# Page_1.net
KiCad netlist of a schematic drawn in Altium Designer
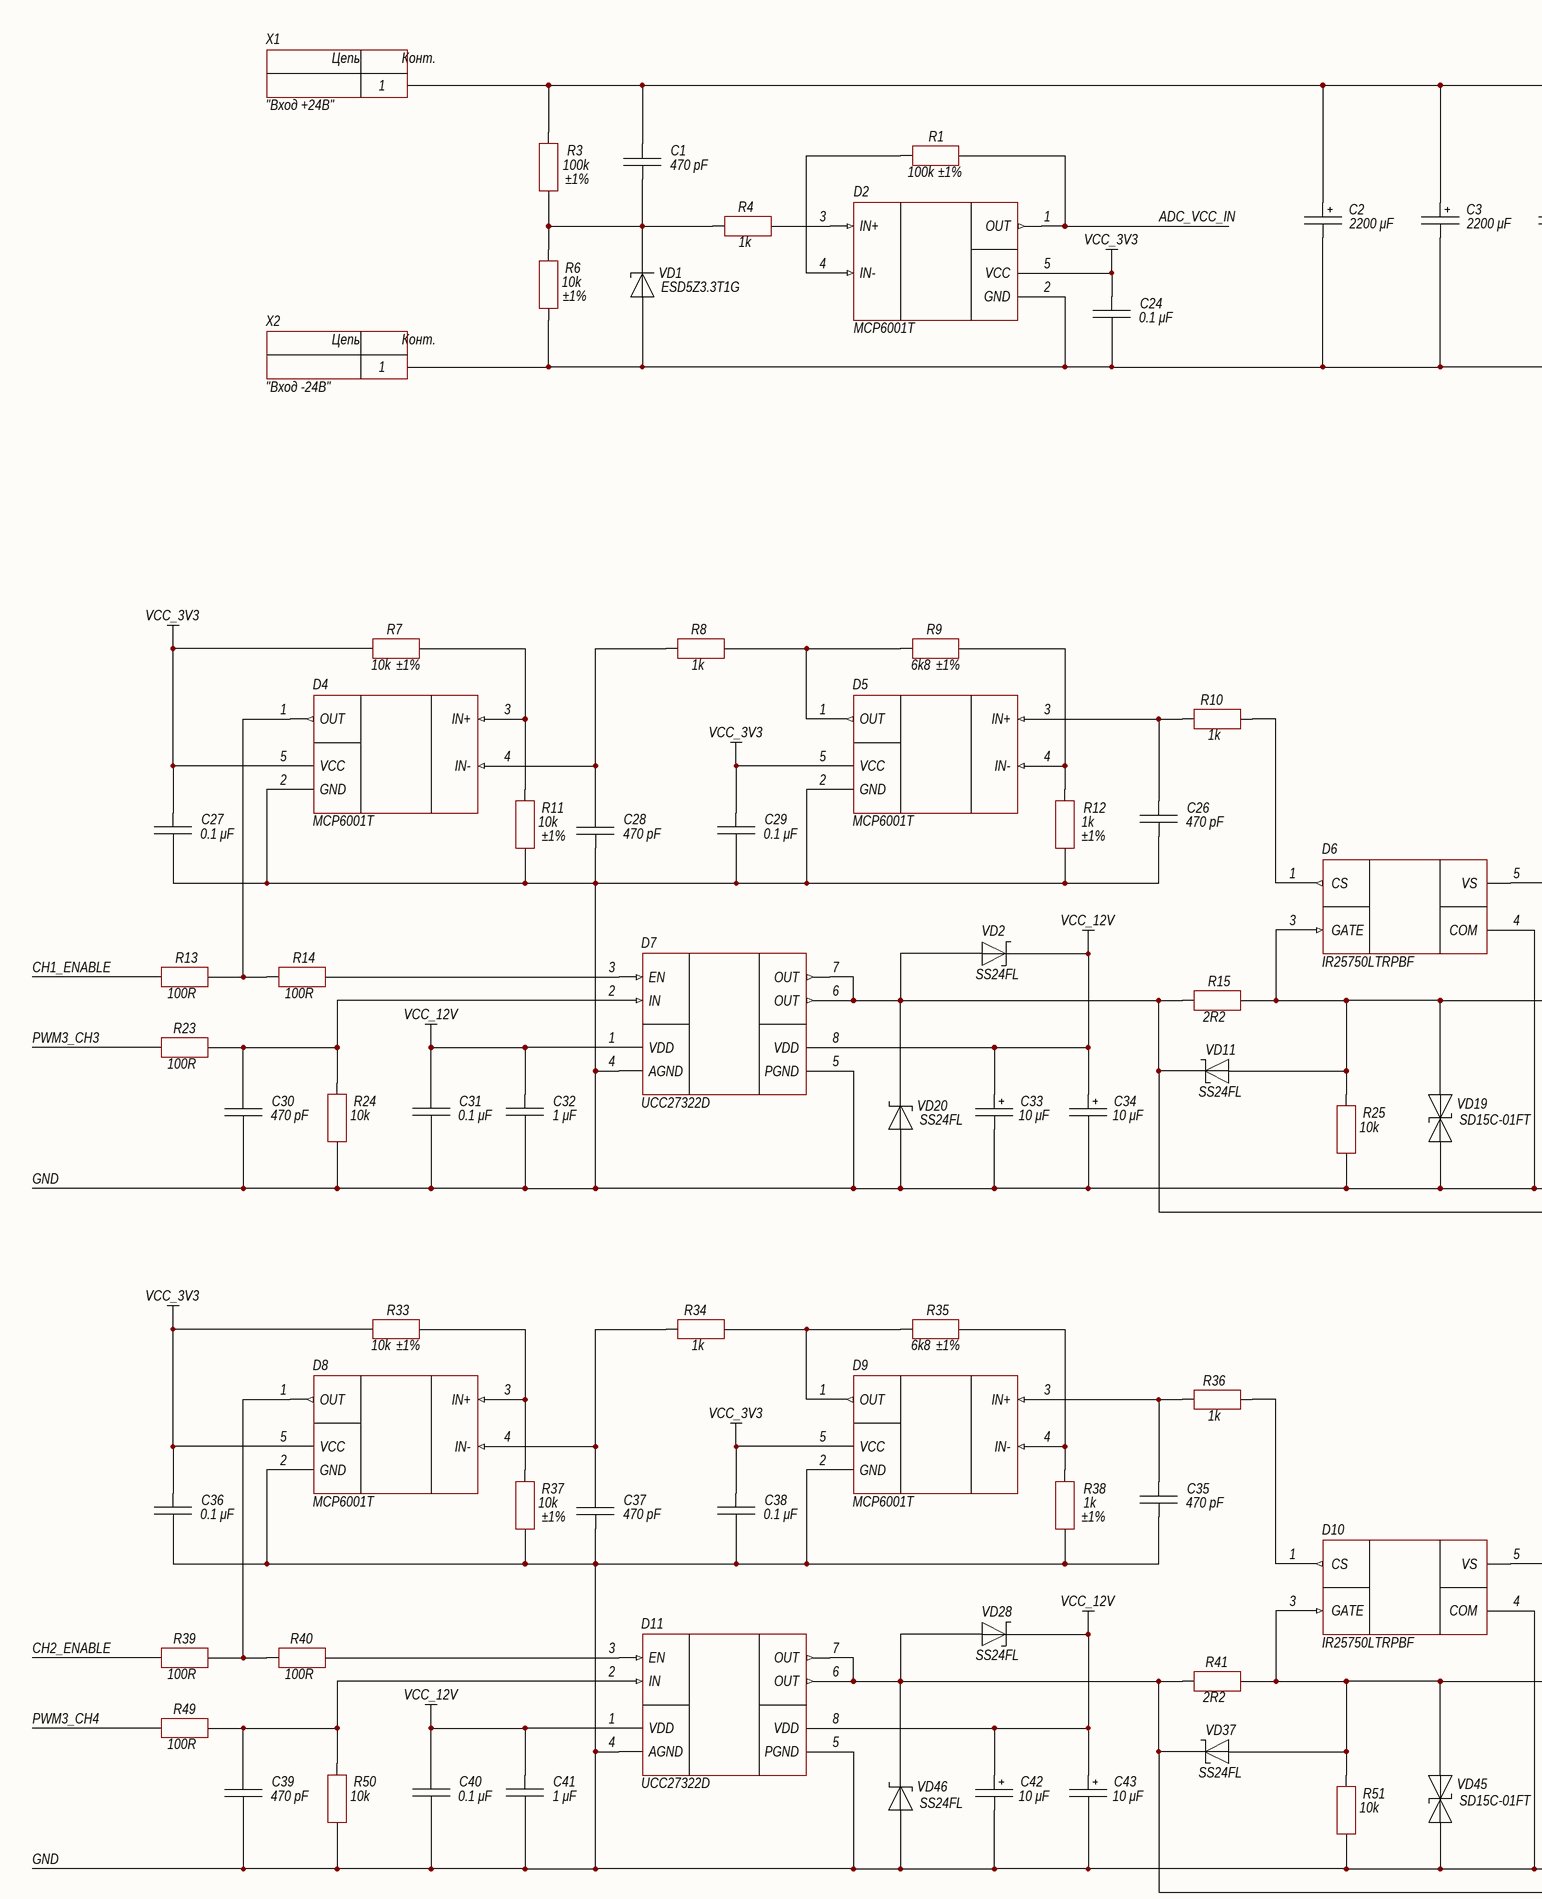
[diagram p0: Page 1.SchDoc, top left]
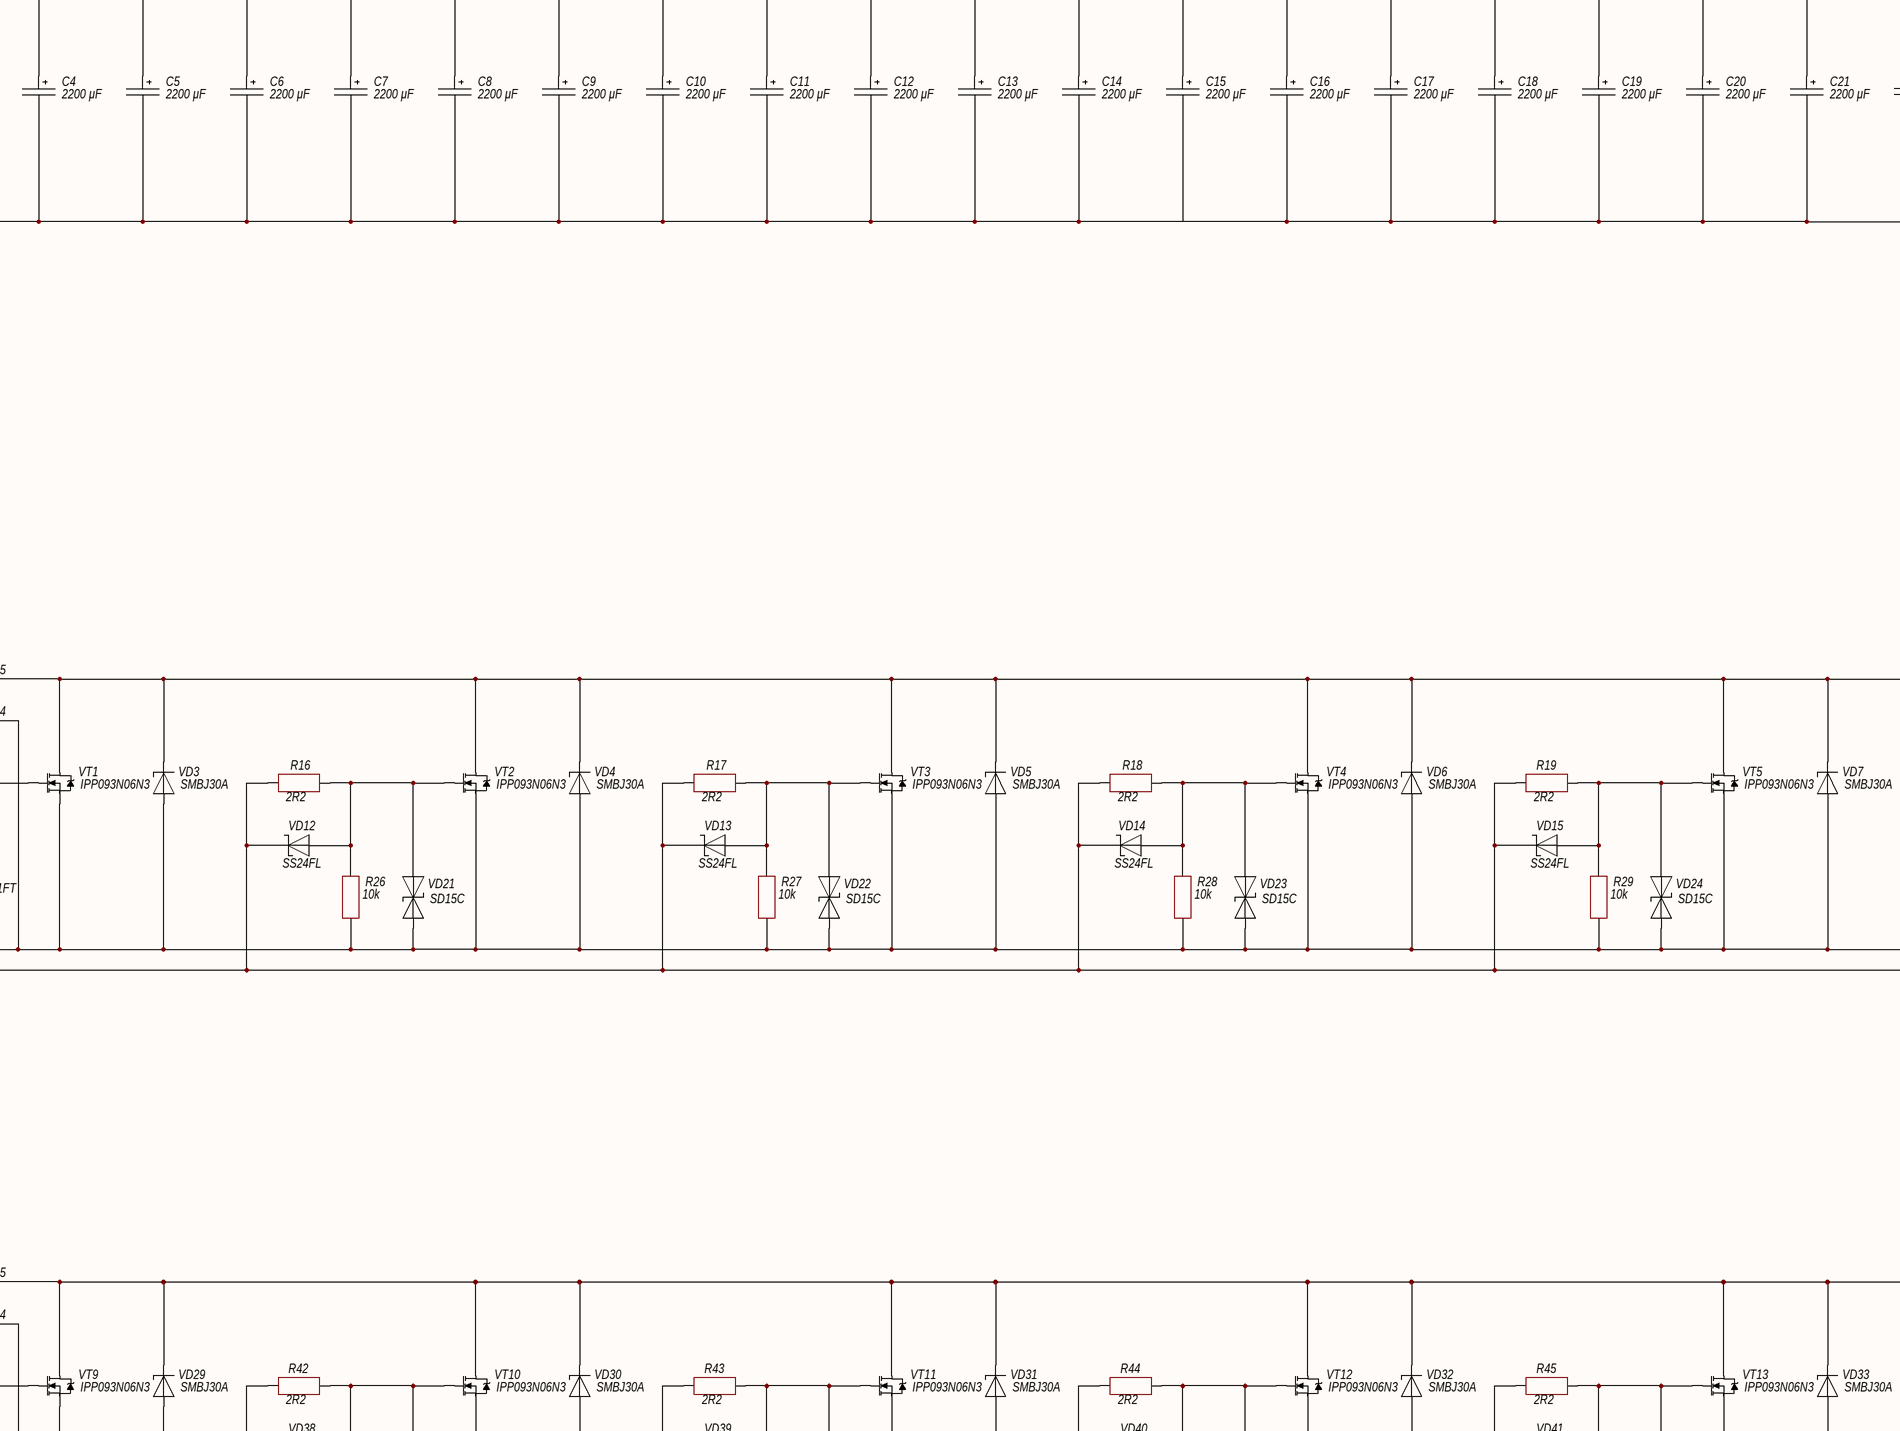
[diagram p1: Page 1.SchDoc, top middle]
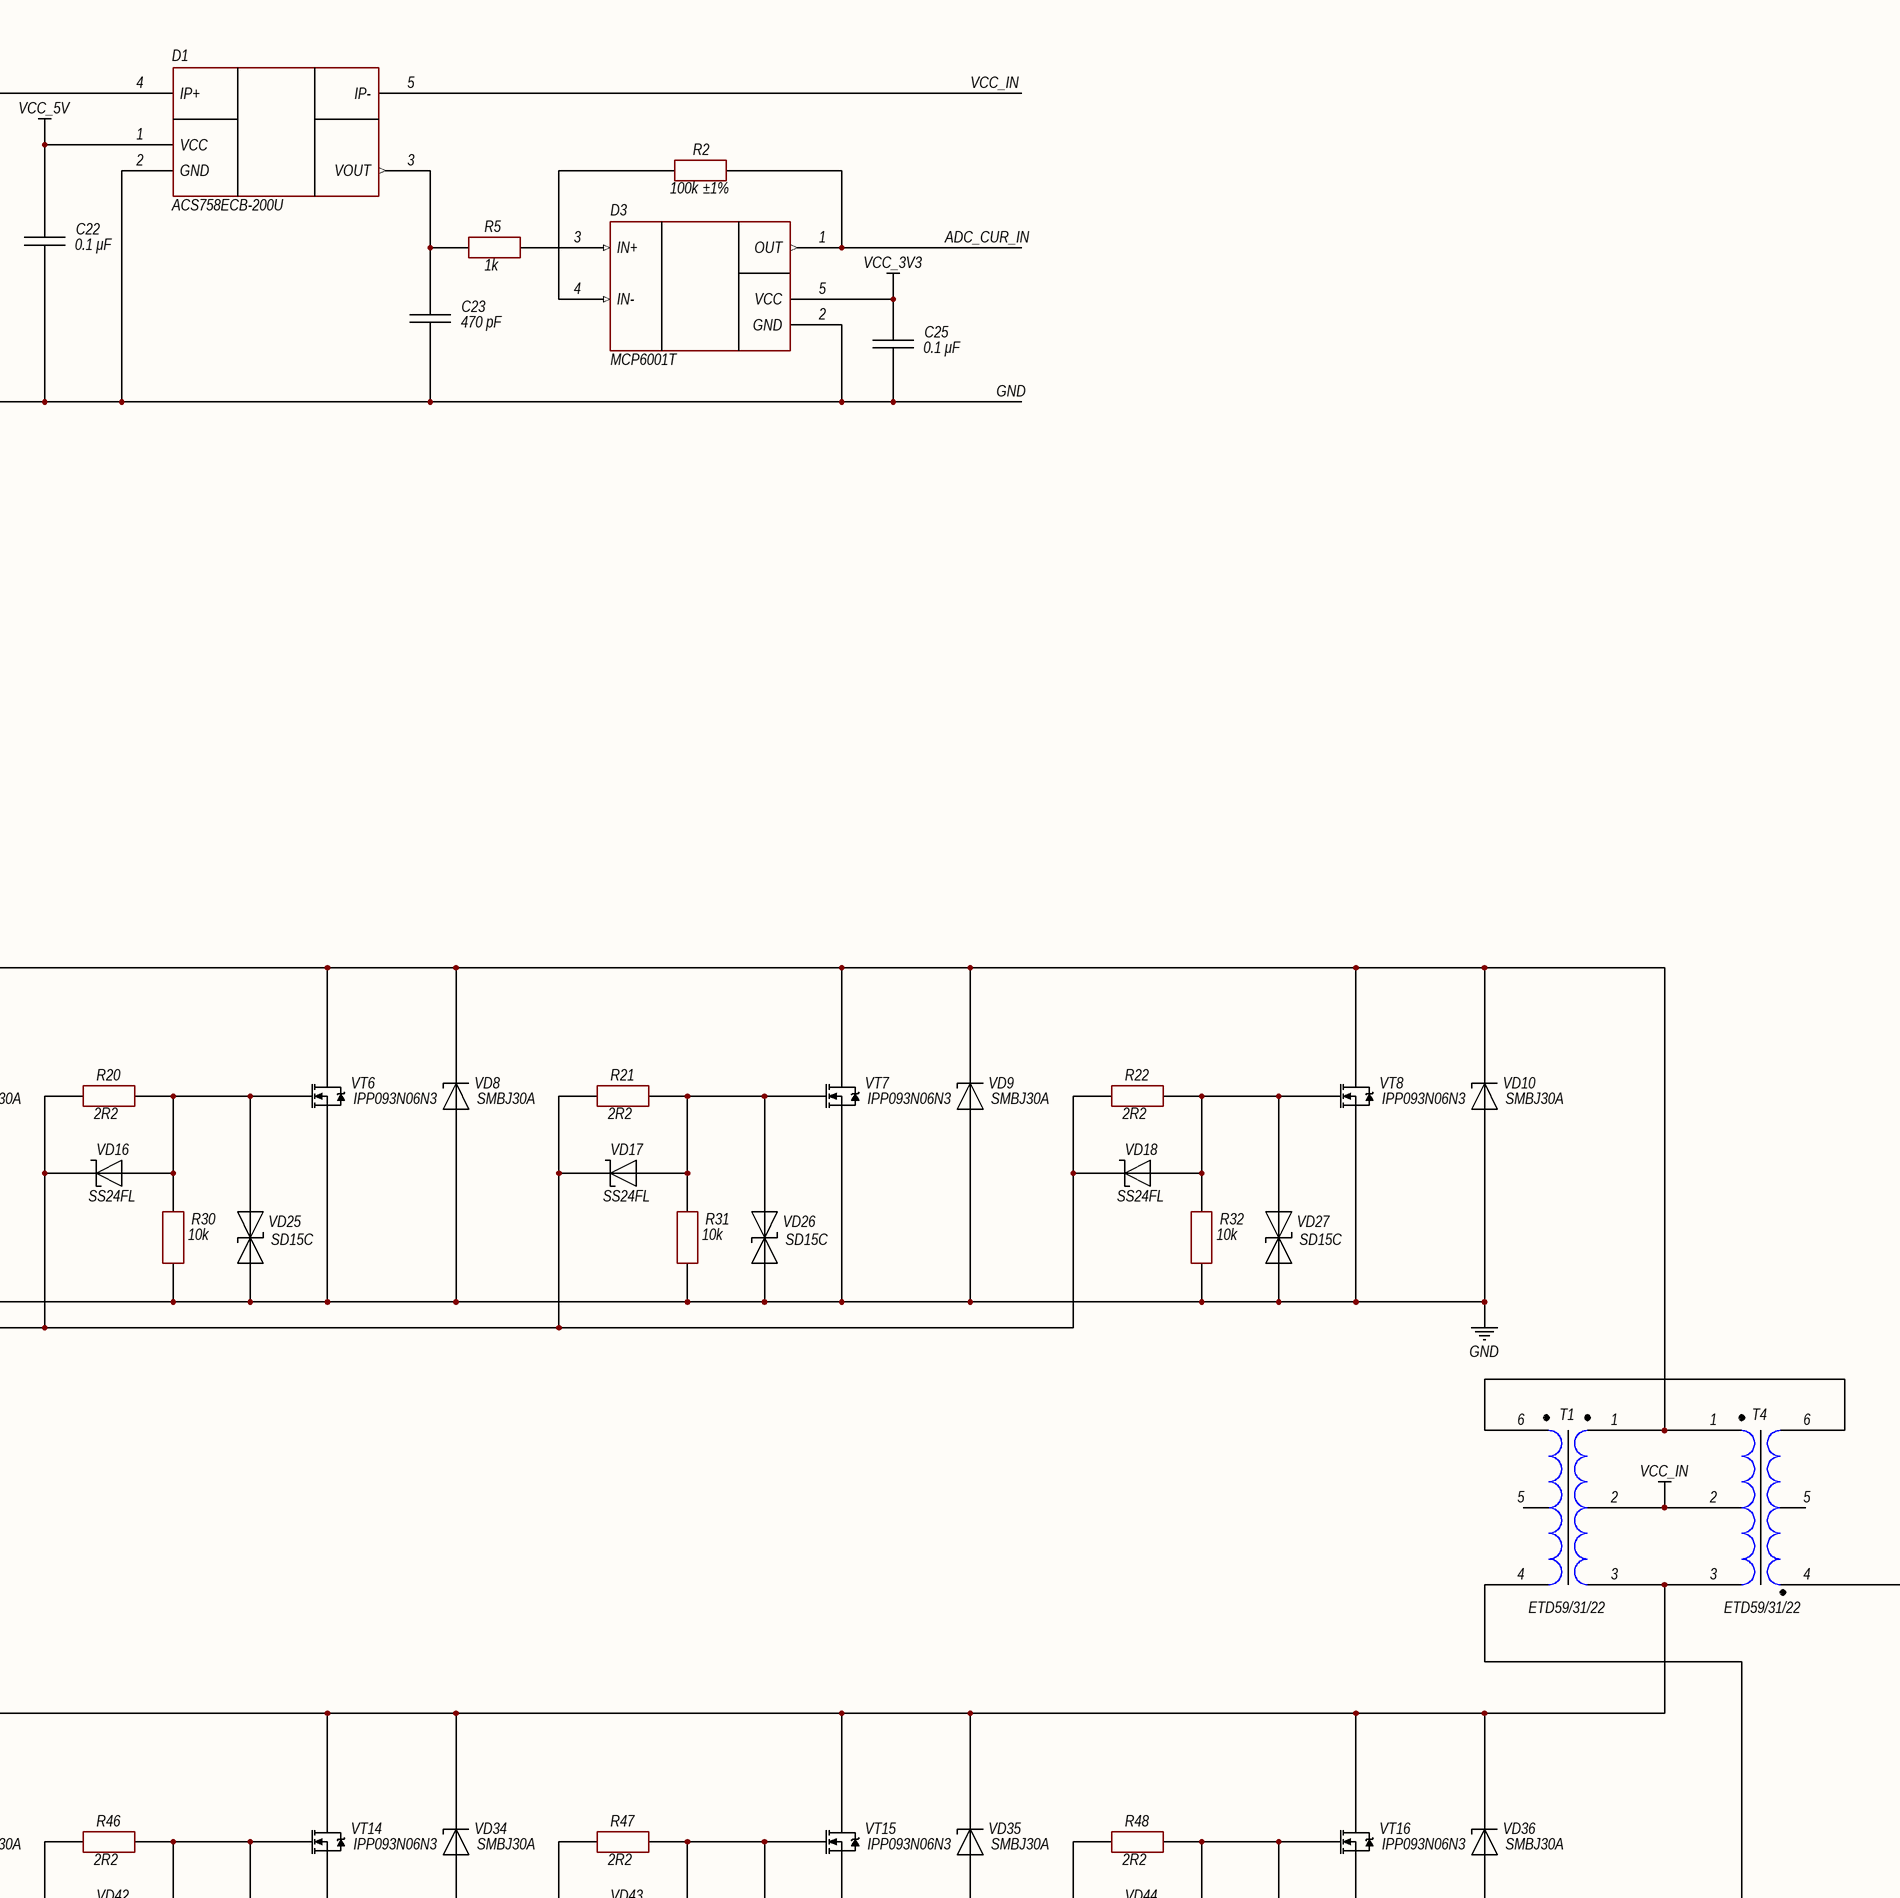
[diagram p2: Page 1.SchDoc, top right]
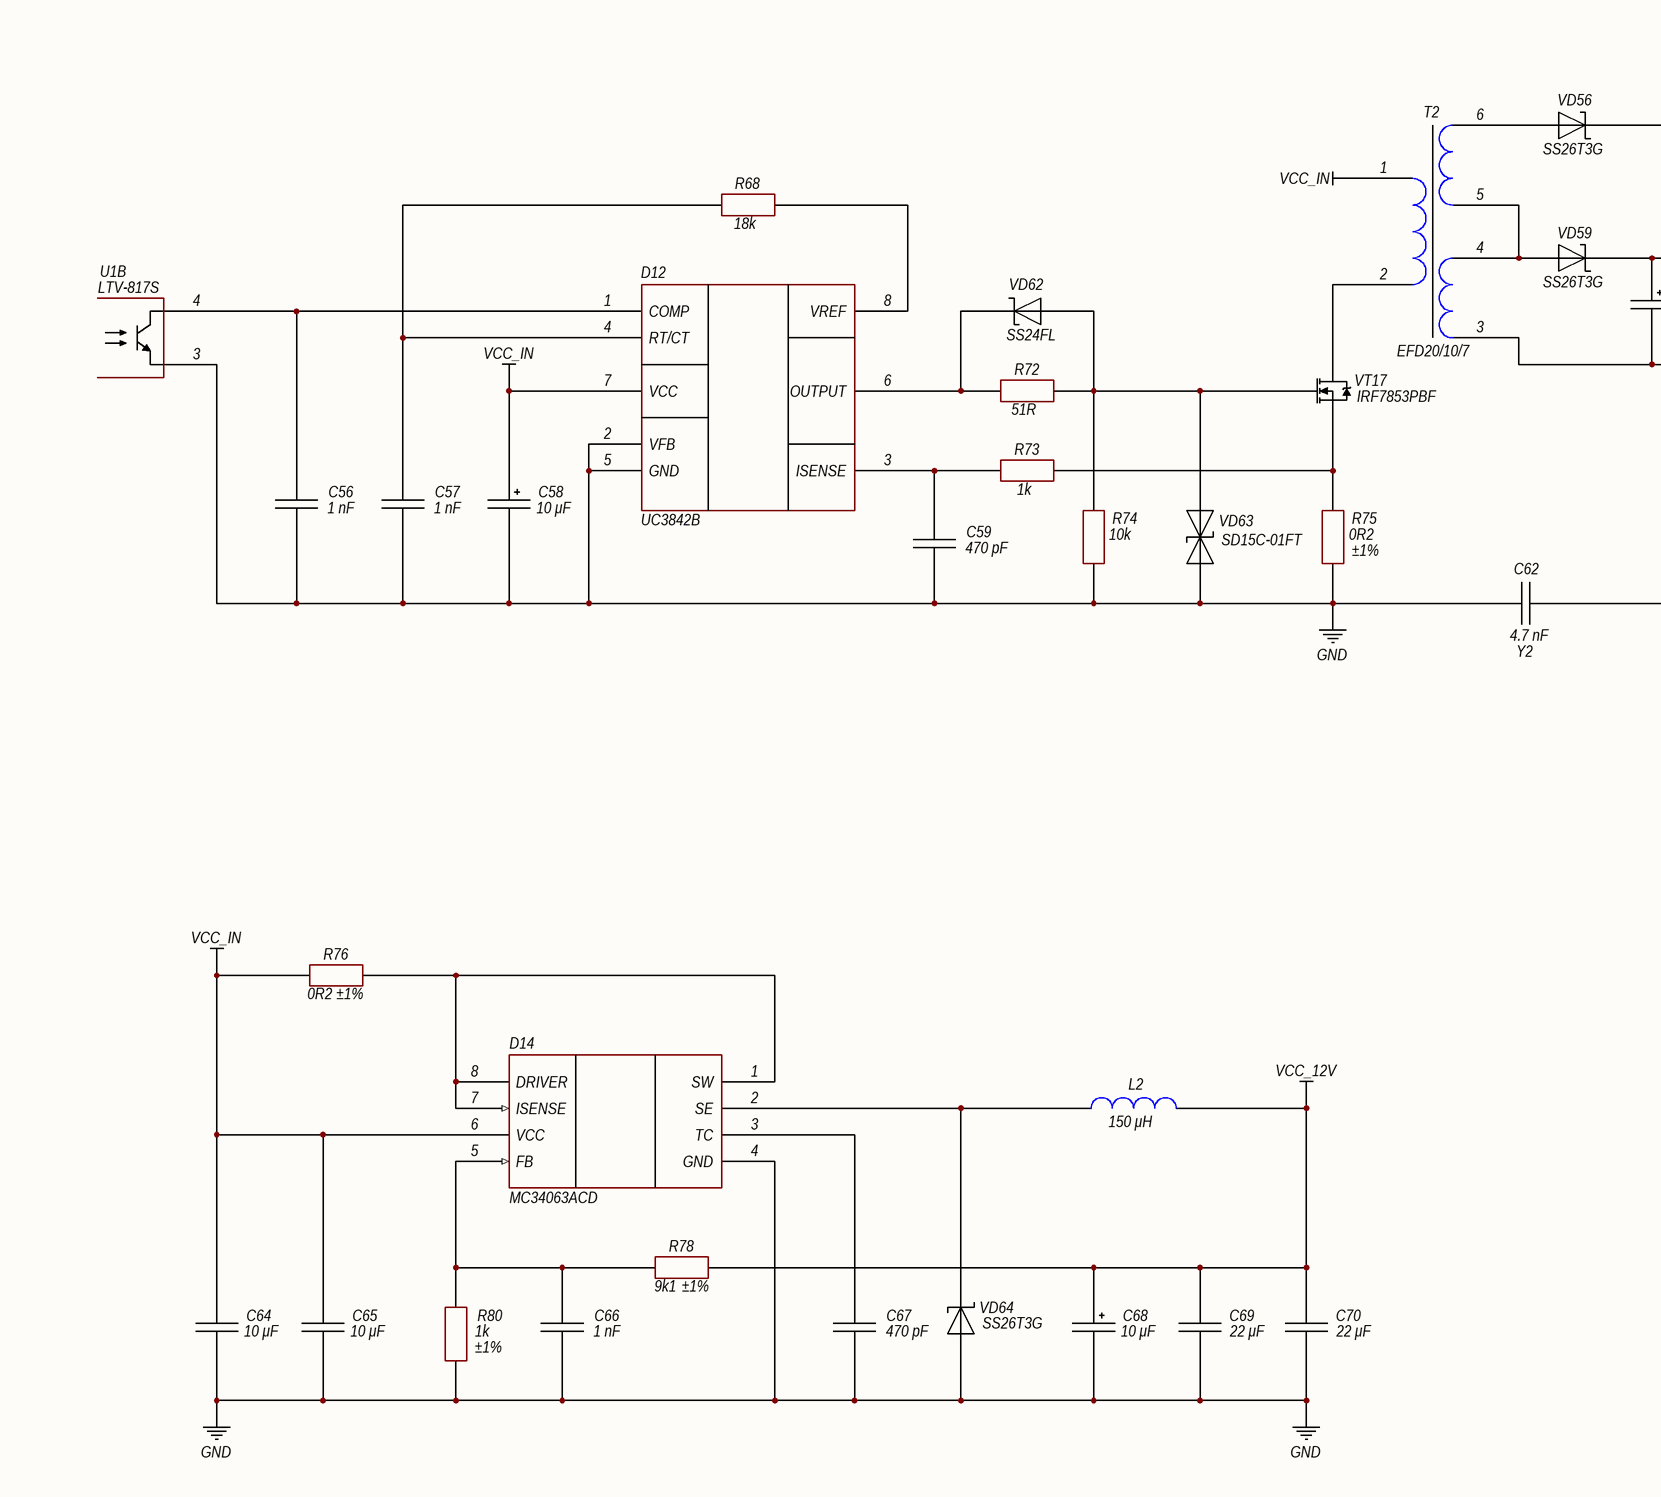
[diagram p3: Page 1.SchDoc, bottom left]
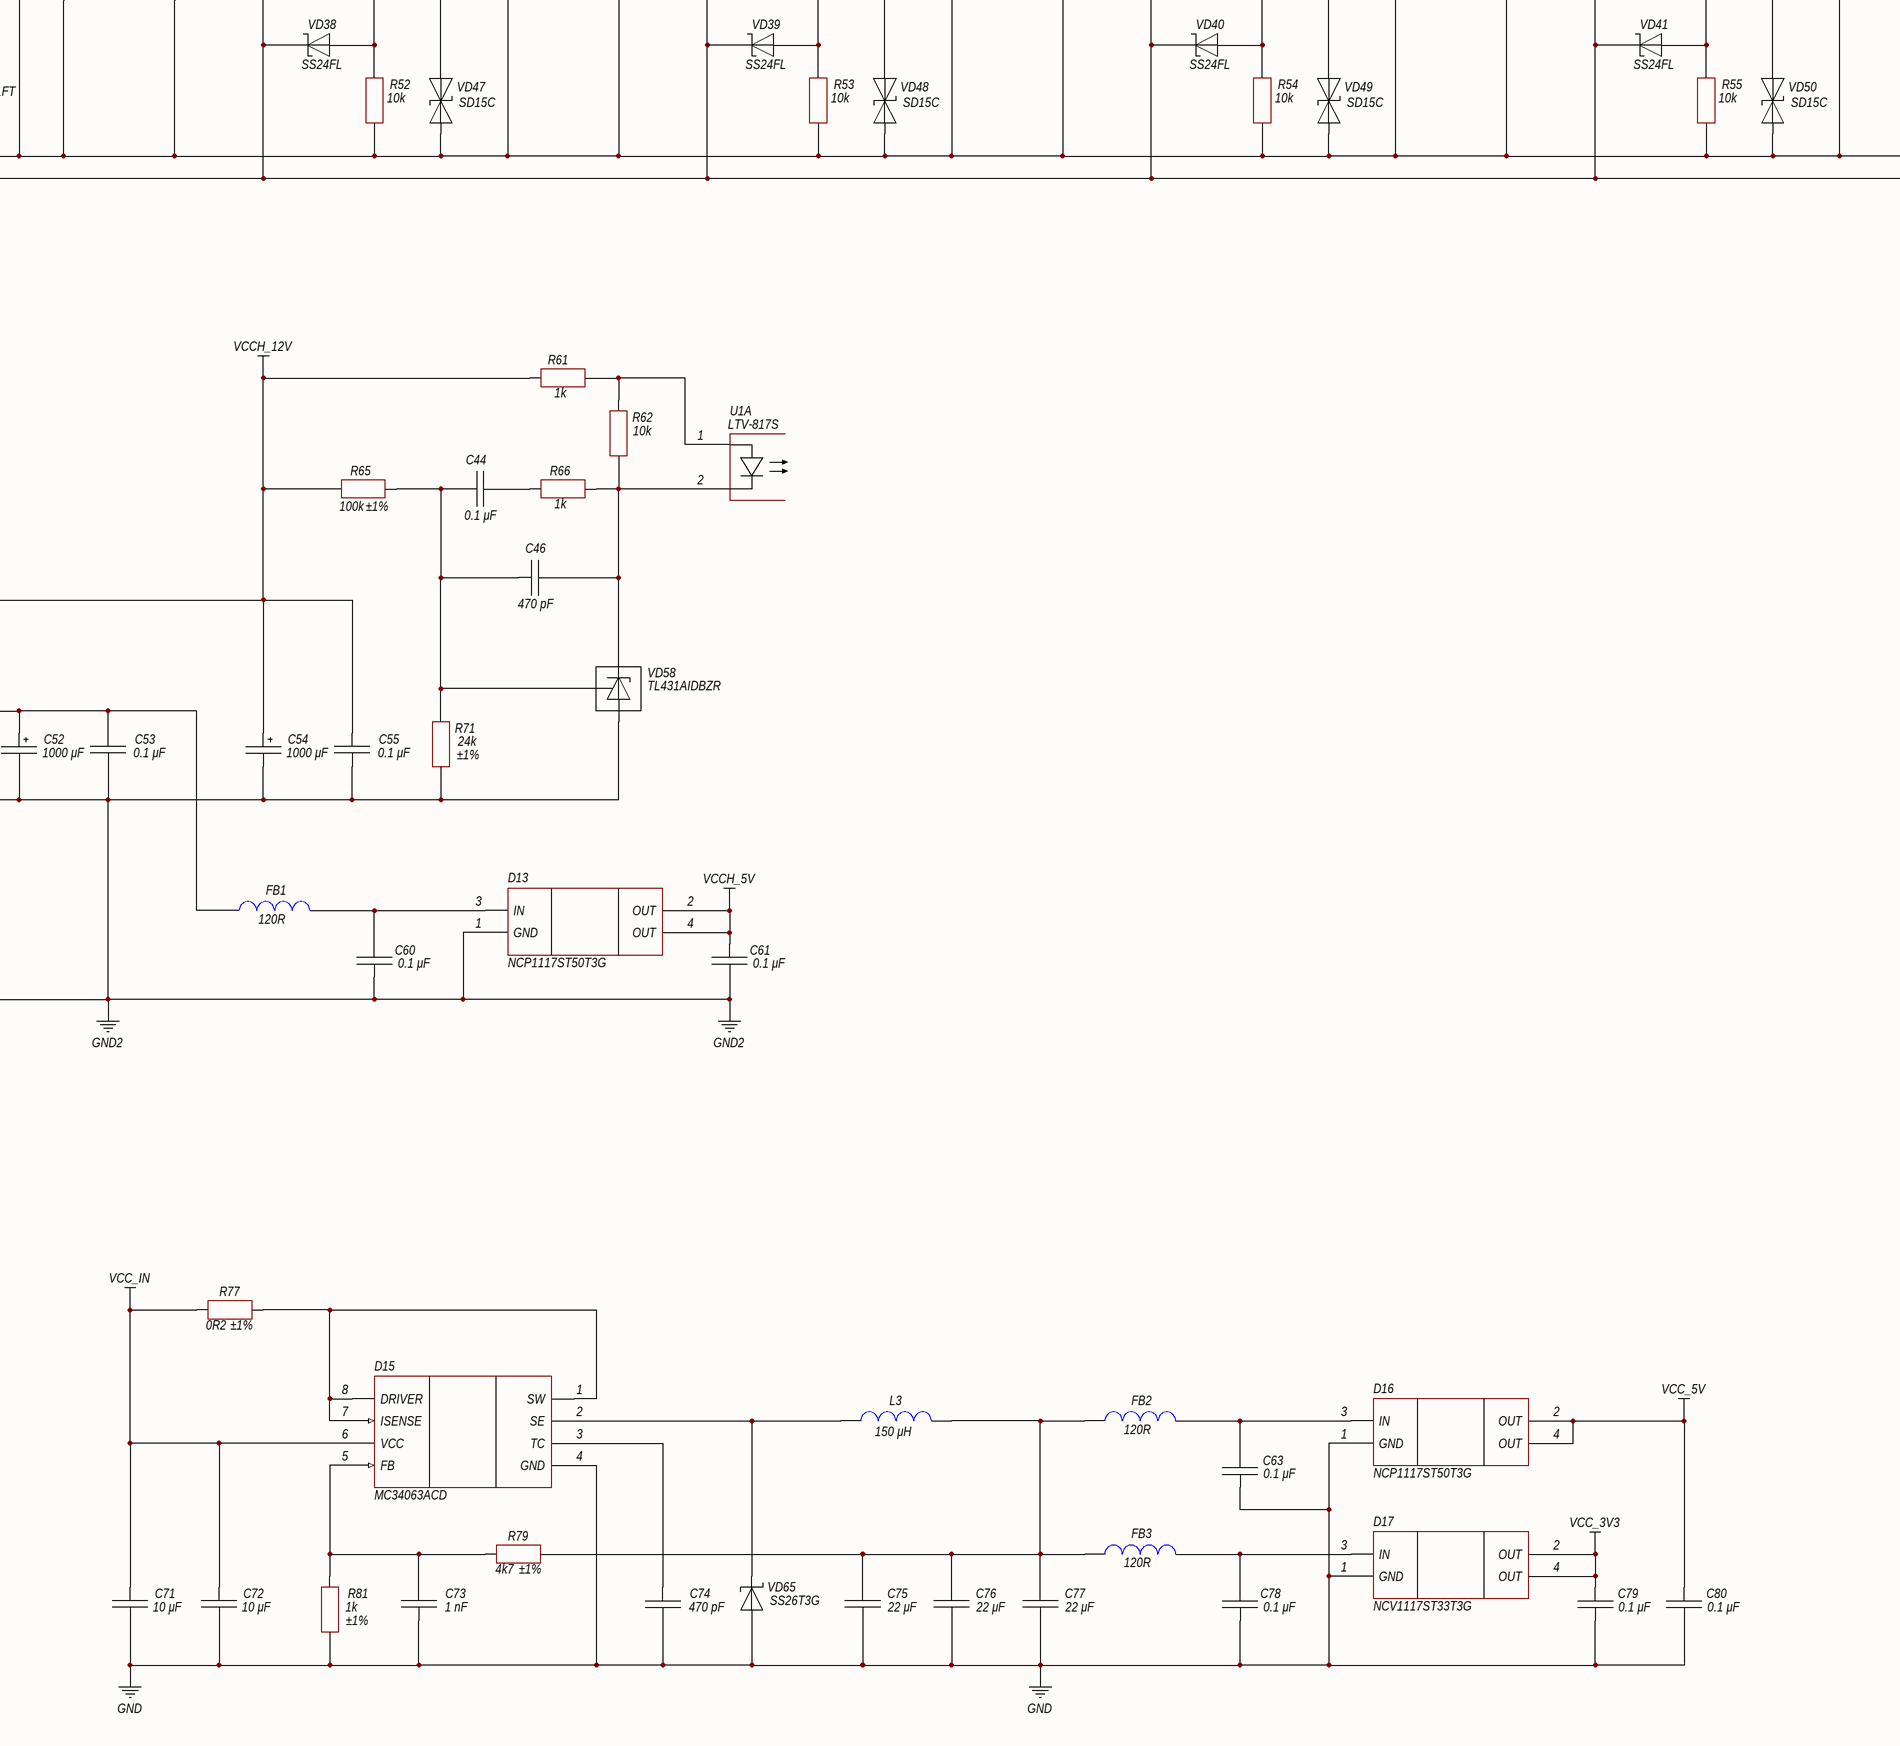
[diagram p4: Page 1.SchDoc, bottom middle]
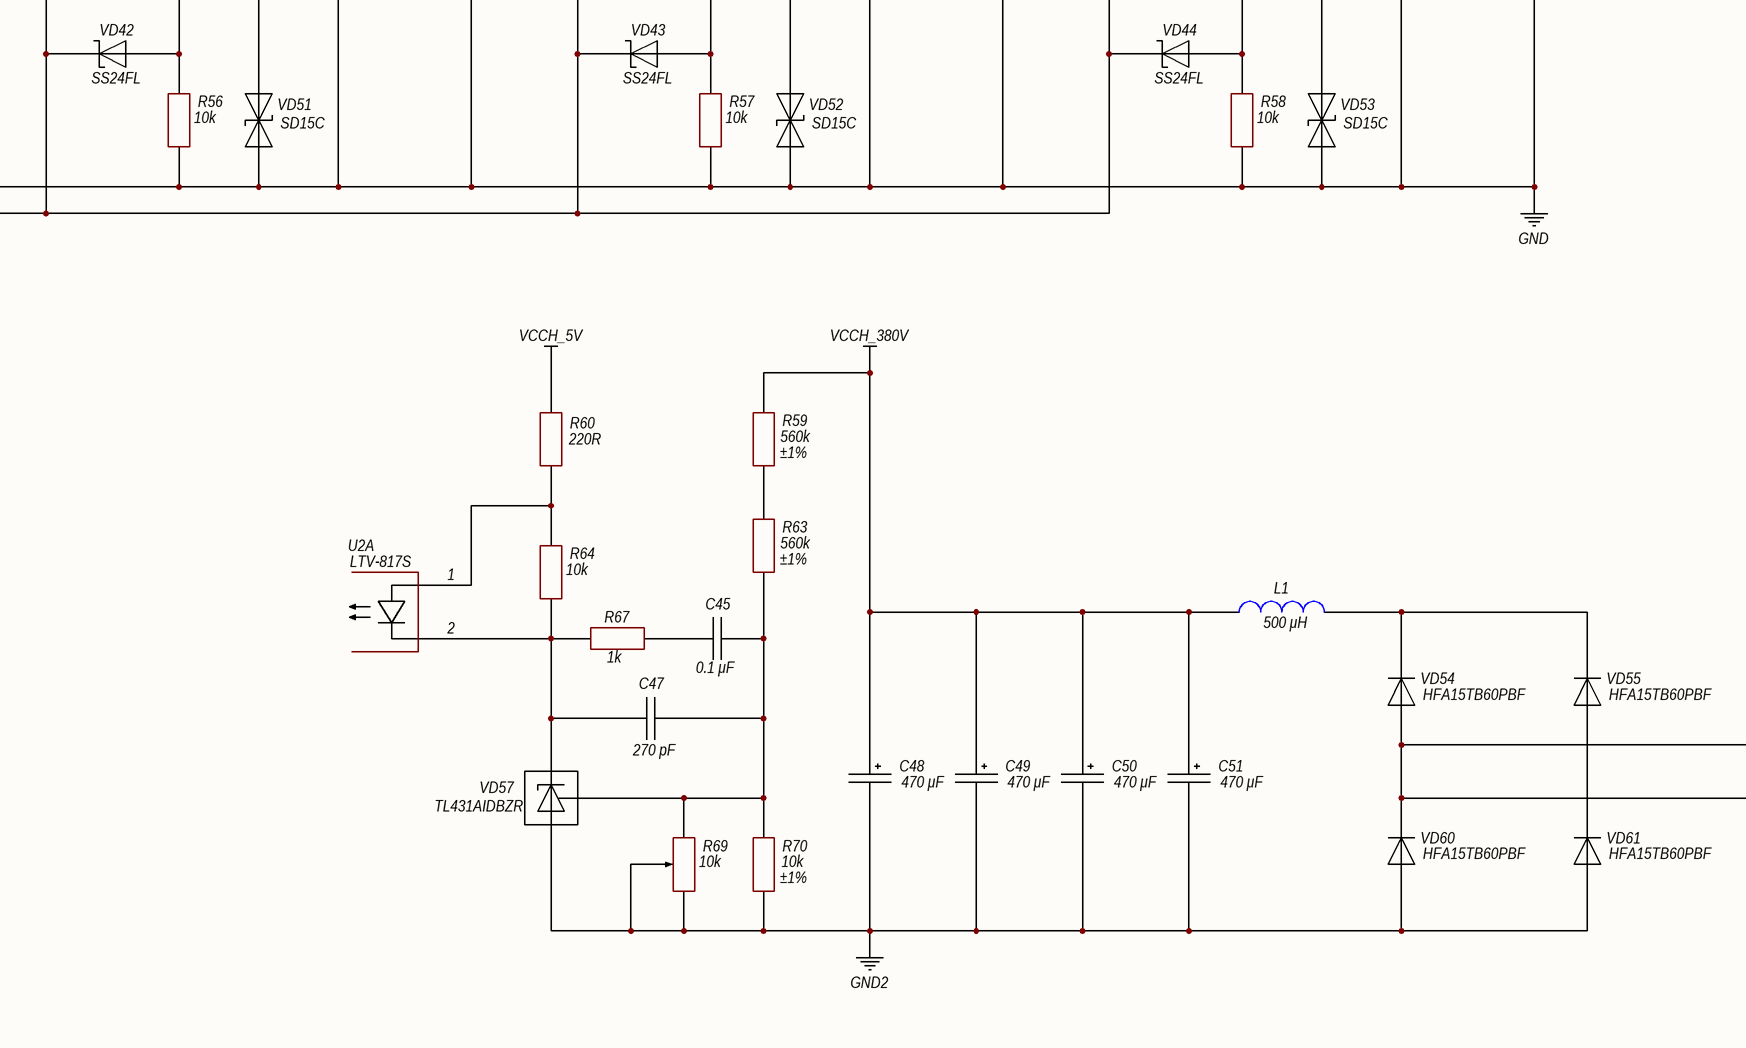
[diagram p5: Page 1.SchDoc, bottom right]

(export (version "E")
  (design (tool "Eeschema 10.0.6"))
  (components
    (comp (ref "C1")
      (value "470 pF")
      (footprint "CH0805C")
      (fields (field (name "MANUFACTURER") "Yageo"))
      (libsource (lib "Discrete") (part "Capacitor"))
    )
    (comp (ref "C2")
      (value "2200 μF")
      (footprint "D16C7.5H25")
      (fields (field (name "MANUFACTURER") "Epcos"))
      (libsource (lib "Discrete") (part "AlumCap"))
    )
    (comp (ref "C3")
      (value "2200 μF")
      (footprint "D16C7.5H25")
      (fields (field (name "MANUFACTURER") "Epcos"))
      (libsource (lib "Discrete") (part "AlumCap"))
    )
    (comp (ref "C4")
      (value "2200 μF")
      (footprint "D16C7.5H25")
      (fields (field (name "MANUFACTURER") "Epcos"))
      (libsource (lib "Discrete") (part "AlumCap"))
    )
    (comp (ref "C5")
      (value "2200 μF")
      (footprint "D16C7.5H25")
      (fields (field (name "MANUFACTURER") "Epcos"))
      (libsource (lib "Discrete") (part "AlumCap"))
    )
    (comp (ref "C6")
      (value "2200 μF")
      (footprint "D16C7.5H25")
      (fields (field (name "MANUFACTURER") "Epcos"))
      (libsource (lib "Discrete") (part "AlumCap"))
    )
    (comp (ref "C7")
      (value "2200 μF")
      (footprint "D16C7.5H25")
      (fields (field (name "MANUFACTURER") "Epcos"))
      (libsource (lib "Discrete") (part "AlumCap"))
    )
    (comp (ref "C8")
      (value "2200 μF")
      (footprint "D16C7.5H25")
      (fields (field (name "MANUFACTURER") "Epcos"))
      (libsource (lib "Discrete") (part "AlumCap"))
    )
    (comp (ref "C9")
      (value "2200 μF")
      (footprint "D16C7.5H25")
      (fields (field (name "MANUFACTURER") "Epcos"))
      (libsource (lib "Discrete") (part "AlumCap"))
    )
    (comp (ref "C10")
      (value "2200 μF")
      (footprint "D16C7.5H25")
      (fields (field (name "MANUFACTURER") "Epcos"))
      (libsource (lib "Discrete") (part "AlumCap"))
    )
    (comp (ref "C11")
      (value "2200 μF")
      (footprint "D16C7.5H25")
      (fields (field (name "MANUFACTURER") "Epcos"))
      (libsource (lib "Discrete") (part "AlumCap"))
    )
    (comp (ref "C12")
      (value "2200 μF")
      (footprint "D16C7.5H25")
      (fields (field (name "MANUFACTURER") "Epcos"))
      (libsource (lib "Discrete") (part "AlumCap"))
    )
    (comp (ref "C13")
      (value "2200 μF")
      (footprint "D16C7.5H25")
      (fields (field (name "MANUFACTURER") "Epcos"))
      (libsource (lib "Discrete") (part "AlumCap"))
    )
    (comp (ref "C14")
      (value "2200 μF")
      (footprint "D16C7.5H25")
      (fields (field (name "MANUFACTURER") "Epcos"))
      (libsource (lib "Discrete") (part "AlumCap"))
    )
    (comp (ref "C15")
      (value "2200 μF")
      (footprint "D16C7.5H25")
      (fields (field (name "MANUFACTURER") "Epcos"))
      (libsource (lib "Discrete") (part "AlumCap"))
    )
    (comp (ref "C16")
      (value "2200 μF")
      (footprint "D16C7.5H25")
      (fields (field (name "MANUFACTURER") "Epcos"))
      (libsource (lib "Discrete") (part "AlumCap"))
    )
    (comp (ref "C17")
      (value "2200 μF")
      (footprint "D16C7.5H25")
      (fields (field (name "MANUFACTURER") "Epcos"))
      (libsource (lib "Discrete") (part "AlumCap"))
    )
    (comp (ref "C18")
      (value "2200 μF")
      (footprint "D16C7.5H25")
      (fields (field (name "MANUFACTURER") "Epcos"))
      (libsource (lib "Discrete") (part "AlumCap"))
    )
    (comp (ref "C19")
      (value "2200 μF")
      (footprint "D16C7.5H25")
      (fields (field (name "MANUFACTURER") "Epcos"))
      (libsource (lib "Discrete") (part "AlumCap"))
    )
    (comp (ref "C20")
      (value "2200 μF")
      (footprint "D16C7.5H25")
      (fields (field (name "MANUFACTURER") "Epcos"))
      (libsource (lib "Discrete") (part "AlumCap"))
    )
    (comp (ref "C21")
      (value "2200 μF")
      (footprint "D16C7.5H25")
      (fields (field (name "MANUFACTURER") "Epcos"))
      (libsource (lib "Discrete") (part "AlumCap"))
    )
    (comp (ref "C22")
      (value "0.1 μF")
      (footprint "CH0805C")
      (fields (field (name "MANUFACTURER") "Yageo"))
      (libsource (lib "Discrete") (part "Capacitor"))
    )
    (comp (ref "C23")
      (value "470 pF")
      (footprint "CH0805C")
      (fields (field (name "MANUFACTURER") "Yageo"))
      (libsource (lib "Discrete") (part "Capacitor"))
    )
    (comp (ref "C24")
      (value "0.1 μF")
      (footprint "CH0805C")
      (fields (field (name "MANUFACTURER") "Yageo"))
      (libsource (lib "Discrete") (part "Capacitor"))
    )
    (comp (ref "C25")
      (value "0.1 μF")
      (footprint "CH0805C")
      (fields (field (name "MANUFACTURER") "Yageo"))
      (libsource (lib "Discrete") (part "Capacitor"))
    )
    (comp (ref "C26")
      (value "470 pF")
      (footprint "CH0805C")
      (fields (field (name "MANUFACTURER") "Yageo"))
      (libsource (lib "Discrete") (part "Capacitor"))
    )
    (comp (ref "C27")
      (value "0.1 μF")
      (footprint "CH0805C")
      (fields (field (name "MANUFACTURER") "Yageo"))
      (libsource (lib "Discrete") (part "Capacitor"))
    )
    (comp (ref "C28")
      (value "470 pF")
      (footprint "CH0805C")
      (fields (field (name "MANUFACTURER") "Yageo"))
      (libsource (lib "Discrete") (part "Capacitor"))
    )
    (comp (ref "C29")
      (value "0.1 μF")
      (footprint "CH0805C")
      (fields (field (name "MANUFACTURER") "Yageo"))
      (libsource (lib "Discrete") (part "Capacitor"))
    )
    (comp (ref "C30")
      (value "470 pF")
      (footprint "CH0805C")
      (fields (field (name "MANUFACTURER") "Yageo"))
      (libsource (lib "Discrete") (part "Capacitor"))
    )
    (comp (ref "C31")
      (value "0.1 μF")
      (footprint "CH0805C")
      (fields (field (name "MANUFACTURER") "Yageo"))
      (libsource (lib "Discrete") (part "Capacitor"))
    )
    (comp (ref "C32")
      (value "1 μF")
      (footprint "CH0805C")
      (fields (field (name "MANUFACTURER") "Yageo"))
      (libsource (lib "Discrete") (part "Capacitor"))
    )
    (comp (ref "C33")
      (value "10 μF")
      (footprint "TANTAL_C")
      (fields (field (name "MANUFACTURER") "Vishay Sprague"))
      (libsource (lib "Discrete") (part "TantalCap"))
    )
    (comp (ref "C34")
      (value "10 μF")
      (footprint "TANTAL_C")
      (fields (field (name "MANUFACTURER") "Vishay Sprague"))
      (libsource (lib "Discrete") (part "TantalCap"))
    )
    (comp (ref "C35")
      (value "470 pF")
      (footprint "CH0805C")
      (fields (field (name "MANUFACTURER") "Yageo"))
      (libsource (lib "Discrete") (part "Capacitor"))
    )
    (comp (ref "C36")
      (value "0.1 μF")
      (footprint "CH0805C")
      (fields (field (name "MANUFACTURER") "Yageo"))
      (libsource (lib "Discrete") (part "Capacitor"))
    )
    (comp (ref "C37")
      (value "470 pF")
      (footprint "CH0805C")
      (fields (field (name "MANUFACTURER") "Yageo"))
      (libsource (lib "Discrete") (part "Capacitor"))
    )
    (comp (ref "C38")
      (value "0.1 μF")
      (footprint "CH0805C")
      (fields (field (name "MANUFACTURER") "Yageo"))
      (libsource (lib "Discrete") (part "Capacitor"))
    )
    (comp (ref "C39")
      (value "470 pF")
      (footprint "CH0805C")
      (fields (field (name "MANUFACTURER") "Yageo"))
      (libsource (lib "Discrete") (part "Capacitor"))
    )
    (comp (ref "C40")
      (value "0.1 μF")
      (footprint "CH0805C")
      (fields (field (name "MANUFACTURER") "Yageo"))
      (libsource (lib "Discrete") (part "Capacitor"))
    )
    (comp (ref "C41")
      (value "1 μF")
      (footprint "CH0805C")
      (fields (field (name "MANUFACTURER") "Yageo"))
      (libsource (lib "Discrete") (part "Capacitor"))
    )
    (comp (ref "C42")
      (value "10 μF")
      (footprint "TANTAL_C")
      (fields (field (name "MANUFACTURER") "Vishay Sprague"))
      (libsource (lib "Discrete") (part "TantalCap"))
    )
    (comp (ref "C43")
      (value "10 μF")
      (footprint "TANTAL_C")
      (fields (field (name "MANUFACTURER") "Vishay Sprague"))
      (libsource (lib "Discrete") (part "TantalCap"))
    )
    (comp (ref "C44")
      (value "0.1 μF")
      (footprint "CH0805C")
      (fields (field (name "MANUFACTURER") "Yageo"))
      (libsource (lib "Discrete") (part "Capacitor"))
    )
    (comp (ref "C45")
      (value "0.1 μF")
      (footprint "CH0805C")
      (fields (field (name "MANUFACTURER") "Yageo"))
      (libsource (lib "Discrete") (part "Capacitor"))
    )
    (comp (ref "C46")
      (value "470 pF")
      (footprint "CH0805C")
      (fields (field (name "MANUFACTURER") "Yageo"))
      (libsource (lib "Discrete") (part "Capacitor"))
    )
    (comp (ref "C47")
      (value "270 pF")
      (footprint "CH0805C")
      (fields (field (name "MANUFACTURER") "Yageo"))
      (libsource (lib "Discrete") (part "Capacitor"))
    )
    (comp (ref "C48")
      (value "470 μF")
      (footprint "D35C10.5H50")
      (fields (field (name "MANUFACTURER") "EPCOS"))
      (libsource (lib "Discrete") (part "AlumCap"))
    )
    (comp (ref "C49")
      (value "470 μF")
      (footprint "D35C10.5H50")
      (fields (field (name "MANUFACTURER") "EPCOS"))
      (libsource (lib "Discrete") (part "AlumCap"))
    )
    (comp (ref "C50")
      (value "470 μF")
      (footprint "D35C10.5H50")
      (fields (field (name "MANUFACTURER") "EPCOS"))
      (libsource (lib "Discrete") (part "AlumCap"))
    )
    (comp (ref "C51")
      (value "470 μF")
      (footprint "D35C10.5H50")
      (fields (field (name "MANUFACTURER") "EPCOS"))
      (libsource (lib "Discrete") (part "AlumCap"))
    )
    (comp (ref "C52")
      (value "1000 μF")
      (footprint "D10C5H20")
      (fields (field (name "MANUFACTURER") "Epcos"))
      (libsource (lib "Discrete") (part "AlumCap"))
    )
    (comp (ref "C53")
      (value "0.1 μF")
      (footprint "CH0805C")
      (fields (field (name "MANUFACTURER") "Yageo"))
      (libsource (lib "Discrete") (part "Capacitor"))
    )
    (comp (ref "C54")
      (value "1000 μF")
      (footprint "D10C5H20")
      (fields (field (name "MANUFACTURER") "Epcos"))
      (libsource (lib "Discrete") (part "AlumCap"))
    )
    (comp (ref "C55")
      (value "0.1 μF")
      (footprint "CH0805C")
      (fields (field (name "MANUFACTURER") "Yageo"))
      (libsource (lib "Discrete") (part "Capacitor"))
    )
    (comp (ref "C56")
      (value "1 nF")
      (footprint "CH0805C")
      (fields (field (name "MANUFACTURER") "Yageo"))
      (libsource (lib "Discrete") (part "Capacitor"))
    )
    (comp (ref "C57")
      (value "1 nF")
      (footprint "CH0805C")
      (fields (field (name "MANUFACTURER") "Yageo"))
      (libsource (lib "Discrete") (part "Capacitor"))
    )
    (comp (ref "C58")
      (value "10 μF")
      (footprint "TANTAL_C")
      (fields (field (name "MANUFACTURER") "Vishay Sprague"))
      (libsource (lib "Discrete") (part "TantalCap"))
    )
    (comp (ref "C59")
      (value "470 pF")
      (footprint "CH0805C")
      (fields (field (name "MANUFACTURER") "Yageo"))
      (libsource (lib "Discrete") (part "Capacitor"))
    )
    (comp (ref "C60")
      (value "0.1 μF")
      (footprint "CH0805C")
      (fields (field (name "MANUFACTURER") "Yageo"))
      (libsource (lib "Discrete") (part "Capacitor"))
    )
    (comp (ref "C61")
      (value "0.1 μF")
      (footprint "CH0805C")
      (fields (field (name "MANUFACTURER") "Yageo"))
      (libsource (lib "Discrete") (part "Capacitor"))
    )
    (comp (ref "C62")
      (value "4.7 nF")
      (footprint "CAP: B32021")
      (fields (field (name "MANUFACTURER") "EPCOS (TDK)") (field (name "COMPONENTKIND") "Y2"))
      (libsource (lib "Discrete") (part "Capacitor"))
    )
    (comp (ref "C63")
      (value "0.1 μF")
      (footprint "CH0805C")
      (fields (field (name "MANUFACTURER") "Yageo"))
      (libsource (lib "Discrete") (part "Capacitor"))
    )
    (comp (ref "C64")
      (value "10 μF")
      (footprint "CH1206C")
      (fields (field (name "MANUFACTURER") "Yageo"))
      (libsource (lib "Discrete") (part "Capacitor"))
    )
    (comp (ref "C65")
      (value "10 μF")
      (footprint "CH1206C")
      (fields (field (name "MANUFACTURER") "Yageo"))
      (libsource (lib "Discrete") (part "Capacitor"))
    )
    (comp (ref "C66")
      (value "1 nF")
      (footprint "CH0805C")
      (fields (field (name "MANUFACTURER") "Yageo"))
      (libsource (lib "Discrete") (part "Capacitor"))
    )
    (comp (ref "C67")
      (value "470 pF")
      (footprint "CH0805C")
      (fields (field (name "MANUFACTURER") "Yageo"))
      (libsource (lib "Discrete") (part "Capacitor"))
    )
    (comp (ref "C68")
      (value "10 μF")
      (footprint "TANTAL_C")
      (fields (field (name "MANUFACTURER") "Vishay Sprague"))
      (libsource (lib "Discrete") (part "TantalCap"))
    )
    (comp (ref "C69")
      (value "22 μF")
      (footprint "CH1206C")
      (fields (field (name "MANUFACTURER") "Yageo"))
      (libsource (lib "Discrete") (part "Capacitor"))
    )
    (comp (ref "C70")
      (value "22 μF")
      (footprint "CH1206C")
      (fields (field (name "MANUFACTURER") "Yageo"))
      (libsource (lib "Discrete") (part "Capacitor"))
    )
    (comp (ref "C71")
      (value "10 μF")
      (footprint "CH1206C")
      (fields (field (name "MANUFACTURER") "Yageo"))
      (libsource (lib "Discrete") (part "Capacitor"))
    )
    (comp (ref "C72")
      (value "10 μF")
      (footprint "CH1206C")
      (fields (field (name "MANUFACTURER") "Yageo"))
      (libsource (lib "Discrete") (part "Capacitor"))
    )
    (comp (ref "C73")
      (value "1 nF")
      (footprint "CH0805C")
      (fields (field (name "MANUFACTURER") "Yageo"))
      (libsource (lib "Discrete") (part "Capacitor"))
    )
    (comp (ref "C74")
      (value "470 pF")
      (footprint "CH0805C")
      (fields (field (name "MANUFACTURER") "Yageo"))
      (libsource (lib "Discrete") (part "Capacitor"))
    )
    (comp (ref "C75")
      (value "22 μF")
      (footprint "CH1206C")
      (fields (field (name "MANUFACTURER") "Yageo"))
      (libsource (lib "Discrete") (part "Capacitor"))
    )
    (comp (ref "C76")
      (value "22 μF")
      (footprint "CH1206C")
      (fields (field (name "MANUFACTURER") "Yageo"))
      (libsource (lib "Discrete") (part "Capacitor"))
    )
    (comp (ref "C77")
      (value "22 μF")
      (footprint "CH1206C")
      (fields (field (name "MANUFACTURER") "Yageo"))
      (libsource (lib "Discrete") (part "Capacitor"))
    )
    (comp (ref "C78")
      (value "0.1 μF")
      (footprint "CH0805C")
      (fields (field (name "MANUFACTURER") "Yageo"))
      (libsource (lib "Discrete") (part "Capacitor"))
    )
    (comp (ref "C79")
      (value "0.1 μF")
      (footprint "CH0805C")
      (fields (field (name "MANUFACTURER") "Yageo"))
      (libsource (lib "Discrete") (part "Capacitor"))
    )
    (comp (ref "C80")
      (value "0.1 μF")
      (footprint "CH0805C")
      (fields (field (name "MANUFACTURER") "Yageo"))
      (libsource (lib "Discrete") (part "Capacitor"))
    )
    (comp (ref "D1")
      (value "ACS758ECB-200U")
      (footprint "IC: ACS770")
      (description "Sensor")
      (fields (field (name "MANUFACTURER") "Allegro MicroSystems, LLC"))
      (libsource (lib "Power Supplies") (part "ACS770LCB"))
    )
    (comp (ref "D2")
      (value "MCP6001T")
      (footprint "SOT23-5")
      (description "OP amplifier")
      (fields (field (name "MANUFACTURER") "Microchip Technology"))
      (libsource (lib "Analog") (part "MCP6001T"))
    )
    (comp (ref "D3")
      (value "MCP6001T")
      (footprint "SOT23-5")
      (description "OP amplifier")
      (fields (field (name "MANUFACTURER") "Microchip Technology"))
      (libsource (lib "Analog") (part "MCP6001T"))
    )
    (comp (ref "D4")
      (value "MCP6001T")
      (footprint "SOT23-5")
      (description "OP amplifier")
      (fields (field (name "MANUFACTURER") "Microchip Technology"))
      (libsource (lib "") (part "MCP6001T_1"))
    )
    (comp (ref "D5")
      (value "MCP6001T")
      (footprint "SOT23-5")
      (description "OP amplifier")
      (fields (field (name "MANUFACTURER") "Microchip Technology"))
      (libsource (lib "") (part "MCP6001T_1"))
    )
    (comp (ref "D6")
      (value "IR25750LTRPBF")
      (footprint "SOT23-5")
      (description "Sensor")
      (fields (field (name "MANUFACTURER") "Infineon Technologies"))
      (libsource (lib "Power Supplies") (part "IR25750LTRPBF"))
    )
    (comp (ref "D7")
      (value "UCC27322D")
      (footprint "8-SOIC")
      (description "Low driver")
      (fields (field (name "MANUFACTURER") "Texas Instruments"))
      (libsource (lib "Power Supplies") (part "UCC27322D"))
    )
    (comp (ref "D8")
      (value "MCP6001T")
      (footprint "SOT23-5")
      (description "OP amplifier")
      (fields (field (name "MANUFACTURER") "Microchip Technology"))
      (libsource (lib "") (part "MCP6001T_1"))
    )
    (comp (ref "D9")
      (value "MCP6001T")
      (footprint "SOT23-5")
      (description "OP amplifier")
      (fields (field (name "MANUFACTURER") "Microchip Technology"))
      (libsource (lib "") (part "MCP6001T_1"))
    )
    (comp (ref "D10")
      (value "IR25750LTRPBF")
      (footprint "SOT23-5")
      (description "Sensor")
      (fields (field (name "MANUFACTURER") "Infineon Technologies"))
      (libsource (lib "Power Supplies") (part "IR25750LTRPBF"))
    )
    (comp (ref "D11")
      (value "UCC27322D")
      (footprint "8-SOIC")
      (description "Low driver")
      (fields (field (name "MANUFACTURER") "Texas Instruments"))
      (libsource (lib "Power Supplies") (part "UCC27322D"))
    )
    (comp (ref "D12")
      (value "UC3842B")
      (footprint "8-SOIC")
      (description "AC-DC")
      (fields (field (name "MANUFACTURER") "Texas Instruments"))
      (libsource (lib "Power Supplies") (part "UC3842BVD1R2G"))
    )
    (comp (ref "D13")
      (value "NCP1117ST50T3G")
      (footprint "SOT223")
      (description "LDO")
      (fields (field (name "MANUFACTURER") "ON Semiconductor"))
      (libsource (lib "Power Supplies") (part "NCP1117LPST50T3G"))
    )
    (comp (ref "D14")
      (value "MC34063ACD")
      (footprint "8-SOIC")
      (description "Sensor")
      (fields (field (name "MANUFACTURER") "STMicroelectronics"))
      (libsource (lib "Power Supplies") (part "MC34063ADR"))
    )
    (comp (ref "D15")
      (value "MC34063ACD")
      (footprint "8-SOIC")
      (description "Sensor")
      (fields (field (name "MANUFACTURER") "STMicroelectronics"))
      (libsource (lib "Power Supplies") (part "MC34063ADR"))
    )
    (comp (ref "D16")
      (value "NCP1117ST50T3G")
      (footprint "SOT223")
      (description "LDO")
      (fields (field (name "MANUFACTURER") "ON Semiconductor"))
      (libsource (lib "Power Supplies") (part "NCP1117LPST50T3G"))
    )
    (comp (ref "D17")
      (value "NCV1117ST33T3G")
      (footprint "SOT223")
      (description "LDO")
      (fields (field (name "MANUFACTURER") "ON Semiconductor"))
      (libsource (lib "Power Supplies") (part "NCP1117LPST50T3G"))
    )
    (comp (ref "FB1")
      (value "120R")
      (footprint "CH0805L")
      (fields (field (name "MANUFACTURER") "Murata Electronics North America"))
      (libsource (lib "Discrete") (part "Inductor"))
    )
    (comp (ref "FB2")
      (value "120R")
      (footprint "CH0805L")
      (fields (field (name "MANUFACTURER") "Murata Electronics North America"))
      (libsource (lib "Discrete") (part "Inductor"))
    )
    (comp (ref "FB3")
      (value "120R")
      (footprint "CH0805L")
      (fields (field (name "MANUFACTURER") "Murata Electronics North America"))
      (libsource (lib "Discrete") (part "Inductor"))
    )
    (comp (ref "L1")
      (value "500 μH")
      (footprint "IND: R46")
      (fields (field (name "MANUFACTURER") "Magnetics"))
      (libsource (lib "Transformers") (part "Inductor ring"))
    )
    (comp (ref "L2")
      (value "150 μH")
      (footprint "IND: B82477G4")
      (fields (field (name "MANUFACTURER") "Epcos"))
      (libsource (lib "Discrete") (part "Inductor"))
    )
    (comp (ref "L3")
      (value "150 μH")
      (footprint "IND: B82477G4")
      (fields (field (name "MANUFACTURER") "Epcos"))
      (libsource (lib "Discrete") (part "Inductor"))
    )
    (comp (ref "R1")
      (value "100k")
      (footprint "CH0805R")
      (fields (field (name "MANUFACTURER") "Yageo") (field (name "COMPONENTKIND") "±1%"))
      (libsource (lib "") (part "Resistor_3"))
    )
    (comp (ref "R2")
      (value "100k")
      (footprint "CH0805R")
      (fields (field (name "MANUFACTURER") "Yageo") (field (name "COMPONENTKIND") "±1%"))
      (libsource (lib "") (part "Resistor_3"))
    )
    (comp (ref "R3")
      (value "100k")
      (footprint "CH0805R")
      (fields (field (name "MANUFACTURER") "Yageo") (field (name "COMPONENTKIND") "±1%"))
      (libsource (lib "Discrete") (part "Resistor"))
    )
    (comp (ref "R4")
      (value "1k")
      (footprint "CH0805R")
      (fields (field (name "MANUFACTURER") "Yageo"))
      (libsource (lib "Discrete") (part "Resistor"))
    )
    (comp (ref "R5")
      (value "1k")
      (footprint "CH0805R")
      (fields (field (name "MANUFACTURER") "Yageo"))
      (libsource (lib "Discrete") (part "Resistor"))
    )
    (comp (ref "R6")
      (value "10k")
      (footprint "CH0805R")
      (fields (field (name "MANUFACTURER") "Yageo") (field (name "COMPONENTKIND") "±1%"))
      (libsource (lib "Discrete") (part "Resistor"))
    )
    (comp (ref "R7")
      (value "10k")
      (footprint "CH0805R")
      (fields (field (name "MANUFACTURER") "Yageo") (field (name "COMPONENTKIND") "±1%"))
      (libsource (lib "") (part "Resistor_2"))
    )
    (comp (ref "R8")
      (value "1k")
      (footprint "CH0805R")
      (fields (field (name "MANUFACTURER") "Yageo"))
      (libsource (lib "Discrete") (part "Resistor"))
    )
    (comp (ref "R9")
      (value "6k8")
      (footprint "CH0805R")
      (fields (field (name "MANUFACTURER") "Yageo") (field (name "COMPONENTKIND") "±1%"))
      (libsource (lib "") (part "Resistor_2"))
    )
    (comp (ref "R10")
      (value "1k")
      (footprint "CH0805R")
      (fields (field (name "MANUFACTURER") "Yageo"))
      (libsource (lib "Discrete") (part "Resistor"))
    )
    (comp (ref "R11")
      (value "10k")
      (footprint "CH0805R")
      (fields (field (name "MANUFACTURER") "Yageo") (field (name "COMPONENTKIND") "±1%"))
      (libsource (lib "Discrete") (part "Resistor"))
    )
    (comp (ref "R12")
      (value "1k")
      (footprint "CH0805R")
      (fields (field (name "MANUFACTURER") "Yageo") (field (name "COMPONENTKIND") "±1%"))
      (libsource (lib "Discrete") (part "Resistor"))
    )
    (comp (ref "R13")
      (value "100R")
      (footprint "CH0805R")
      (fields (field (name "MANUFACTURER") "Yageo"))
      (libsource (lib "") (part "Resistor_2"))
    )
    (comp (ref "R14")
      (value "100R")
      (footprint "CH0805R")
      (fields (field (name "MANUFACTURER") "Yageo"))
      (libsource (lib "") (part "Resistor_2"))
    )
    (comp (ref "R15")
      (value "2R2")
      (footprint "CH0805R")
      (fields (field (name "MANUFACTURER") "Yageo"))
      (libsource (lib "") (part "Resistor_2"))
    )
    (comp (ref "R16")
      (value "2R2")
      (footprint "CH0805R")
      (fields (field (name "MANUFACTURER") "Yageo"))
      (libsource (lib "") (part "Resistor_2"))
    )
    (comp (ref "R17")
      (value "2R2")
      (footprint "CH0805R")
      (fields (field (name "MANUFACTURER") "Yageo"))
      (libsource (lib "") (part "Resistor_2"))
    )
    (comp (ref "R18")
      (value "2R2")
      (footprint "CH0805R")
      (fields (field (name "MANUFACTURER") "Yageo"))
      (libsource (lib "") (part "Resistor_2"))
    )
    (comp (ref "R19")
      (value "2R2")
      (footprint "CH0805R")
      (fields (field (name "MANUFACTURER") "Yageo"))
      (libsource (lib "") (part "Resistor_2"))
    )
    (comp (ref "R20")
      (value "2R2")
      (footprint "CH0805R")
      (fields (field (name "MANUFACTURER") "Yageo"))
      (libsource (lib "") (part "Resistor_2"))
    )
    (comp (ref "R21")
      (value "2R2")
      (footprint "CH0805R")
      (fields (field (name "MANUFACTURER") "Yageo"))
      (libsource (lib "") (part "Resistor_2"))
    )
    (comp (ref "R22")
      (value "2R2")
      (footprint "CH0805R")
      (fields (field (name "MANUFACTURER") "Yageo"))
      (libsource (lib "") (part "Resistor_2"))
    )
    (comp (ref "R23")
      (value "100R")
      (footprint "CH0805R")
      (fields (field (name "MANUFACTURER") "Yageo"))
      (libsource (lib "") (part "Resistor_2"))
    )
    (comp (ref "R24")
      (value "10k")
      (footprint "CH0805R")
      (fields (field (name "MANUFACTURER") "Yageo"))
      (libsource (lib "") (part "Resistor_1"))
    )
    (comp (ref "R25")
      (value "10k")
      (footprint "CH0805R")
      (fields (field (name "MANUFACTURER") "Yageo"))
      (libsource (lib "") (part "Resistor_1"))
    )
    (comp (ref "R26")
      (value "10k")
      (footprint "CH0805R")
      (fields (field (name "MANUFACTURER") "Yageo"))
      (libsource (lib "") (part "Resistor_1"))
    )
    (comp (ref "R27")
      (value "10k")
      (footprint "CH0805R")
      (fields (field (name "MANUFACTURER") "Yageo"))
      (libsource (lib "") (part "Resistor_1"))
    )
    (comp (ref "R28")
      (value "10k")
      (footprint "CH0805R")
      (fields (field (name "MANUFACTURER") "Yageo"))
      (libsource (lib "") (part "Resistor_1"))
    )
    (comp (ref "R29")
      (value "10k")
      (footprint "CH0805R")
      (fields (field (name "MANUFACTURER") "Yageo"))
      (libsource (lib "") (part "Resistor_1"))
    )
    (comp (ref "R30")
      (value "10k")
      (footprint "CH0805R")
      (fields (field (name "MANUFACTURER") "Yageo"))
      (libsource (lib "") (part "Resistor_1"))
    )
    (comp (ref "R31")
      (value "10k")
      (footprint "CH0805R")
      (fields (field (name "MANUFACTURER") "Yageo"))
      (libsource (lib "") (part "Resistor_1"))
    )
    (comp (ref "R32")
      (value "10k")
      (footprint "CH0805R")
      (fields (field (name "MANUFACTURER") "Yageo"))
      (libsource (lib "") (part "Resistor_1"))
    )
    (comp (ref "R33")
      (value "10k")
      (footprint "CH0805R")
      (fields (field (name "MANUFACTURER") "Yageo") (field (name "COMPONENTKIND") "±1%"))
      (libsource (lib "") (part "Resistor_2"))
    )
    (comp (ref "R34")
      (value "1k")
      (footprint "CH0805R")
      (fields (field (name "MANUFACTURER") "Yageo"))
      (libsource (lib "Discrete") (part "Resistor"))
    )
    (comp (ref "R35")
      (value "6k8")
      (footprint "CH0805R")
      (fields (field (name "MANUFACTURER") "Yageo") (field (name "COMPONENTKIND") "±1%"))
      (libsource (lib "") (part "Resistor_2"))
    )
    (comp (ref "R36")
      (value "1k")
      (footprint "CH0805R")
      (fields (field (name "MANUFACTURER") "Yageo"))
      (libsource (lib "Discrete") (part "Resistor"))
    )
    (comp (ref "R37")
      (value "10k")
      (footprint "CH0805R")
      (fields (field (name "MANUFACTURER") "Yageo") (field (name "COMPONENTKIND") "±1%"))
      (libsource (lib "Discrete") (part "Resistor"))
    )
    (comp (ref "R38")
      (value "1k")
      (footprint "CH0805R")
      (fields (field (name "MANUFACTURER") "Yageo") (field (name "COMPONENTKIND") "±1%"))
      (libsource (lib "Discrete") (part "Resistor"))
    )
    (comp (ref "R39")
      (value "100R")
      (footprint "CH0805R")
      (fields (field (name "MANUFACTURER") "Yageo"))
      (libsource (lib "") (part "Resistor_2"))
    )
    (comp (ref "R40")
      (value "100R")
      (footprint "CH0805R")
      (fields (field (name "MANUFACTURER") "Yageo"))
      (libsource (lib "") (part "Resistor_2"))
    )
    (comp (ref "R41")
      (value "2R2")
      (footprint "CH0805R")
      (fields (field (name "MANUFACTURER") "Yageo"))
      (libsource (lib "") (part "Resistor_2"))
    )
    (comp (ref "R42")
      (value "2R2")
      (footprint "CH0805R")
      (fields (field (name "MANUFACTURER") "Yageo"))
      (libsource (lib "") (part "Resistor_2"))
    )
    (comp (ref "R43")
      (value "2R2")
      (footprint "CH0805R")
      (fields (field (name "MANUFACTURER") "Yageo"))
      (libsource (lib "") (part "Resistor_2"))
    )
    (comp (ref "R44")
      (value "2R2")
      (footprint "CH0805R")
      (fields (field (name "MANUFACTURER") "Yageo"))
      (libsource (lib "") (part "Resistor_2"))
    )
    (comp (ref "R45")
      (value "2R2")
      (footprint "CH0805R")
      (fields (field (name "MANUFACTURER") "Yageo"))
      (libsource (lib "") (part "Resistor_2"))
    )
    (comp (ref "R46")
      (value "2R2")
      (footprint "CH0805R")
      (fields (field (name "MANUFACTURER") "Yageo"))
      (libsource (lib "") (part "Resistor_2"))
    )
    (comp (ref "R47")
      (value "2R2")
      (footprint "CH0805R")
      (fields (field (name "MANUFACTURER") "Yageo"))
      (libsource (lib "") (part "Resistor_2"))
    )
    (comp (ref "R48")
      (value "2R2")
      (footprint "CH0805R")
      (fields (field (name "MANUFACTURER") "Yageo"))
      (libsource (lib "") (part "Resistor_2"))
    )
    (comp (ref "R49")
      (value "100R")
      (footprint "CH0805R")
      (fields (field (name "MANUFACTURER") "Yageo"))
      (libsource (lib "") (part "Resistor_2"))
    )
    (comp (ref "R50")
      (value "10k")
      (footprint "CH0805R")
      (fields (field (name "MANUFACTURER") "Yageo"))
      (libsource (lib "") (part "Resistor_1"))
    )
    (comp (ref "R51")
      (value "10k")
      (footprint "CH0805R")
      (fields (field (name "MANUFACTURER") "Yageo"))
      (libsource (lib "") (part "Resistor_1"))
    )
    (comp (ref "R52")
      (value "10k")
      (footprint "CH0805R")
      (fields (field (name "MANUFACTURER") "Yageo"))
      (libsource (lib "") (part "Resistor_1"))
    )
    (comp (ref "R53")
      (value "10k")
      (footprint "CH0805R")
      (fields (field (name "MANUFACTURER") "Yageo"))
      (libsource (lib "") (part "Resistor_1"))
    )
    (comp (ref "R54")
      (value "10k")
      (footprint "CH0805R")
      (fields (field (name "MANUFACTURER") "Yageo"))
      (libsource (lib "") (part "Resistor_1"))
    )
    (comp (ref "R55")
      (value "10k")
      (footprint "CH0805R")
      (fields (field (name "MANUFACTURER") "Yageo"))
      (libsource (lib "") (part "Resistor_1"))
    )
    (comp (ref "R56")
      (value "10k")
      (footprint "CH0805R")
      (fields (field (name "MANUFACTURER") "Yageo"))
      (libsource (lib "") (part "Resistor_1"))
    )
    (comp (ref "R57")
      (value "10k")
      (footprint "CH0805R")
      (fields (field (name "MANUFACTURER") "Yageo"))
      (libsource (lib "") (part "Resistor_1"))
    )
    (comp (ref "R58")
      (value "10k")
      (footprint "CH0805R")
      (fields (field (name "MANUFACTURER") "Yageo"))
      (libsource (lib "") (part "Resistor_1"))
    )
    (comp (ref "R59")
      (value "560k")
      (footprint "CH0805R")
      (fields (field (name "MANUFACTURER") "Yageo") (field (name "COMPONENTKIND") "±1%"))
      (libsource (lib "Discrete") (part "Resistor"))
    )
    (comp (ref "R60")
      (value "220R")
      (footprint "CH0805R")
      (fields (field (name "MANUFACTURER") "Yageo"))
      (libsource (lib "") (part "Resistor_1"))
    )
    (comp (ref "R61")
      (value "1k")
      (footprint "CH0805R")
      (fields (field (name "MANUFACTURER") "Yageo"))
      (libsource (lib "Discrete") (part "Resistor"))
    )
    (comp (ref "R62")
      (value "10k")
      (footprint "CH0805R")
      (fields (field (name "MANUFACTURER") "Yageo"))
      (libsource (lib "") (part "Resistor_3"))
    )
    (comp (ref "R63")
      (value "560k")
      (footprint "CH0805R")
      (fields (field (name "MANUFACTURER") "Yageo") (field (name "COMPONENTKIND") "±1%"))
      (libsource (lib "Discrete") (part "Resistor"))
    )
    (comp (ref "R64")
      (value "10k")
      (footprint "CH0805R")
      (fields (field (name "MANUFACTURER") "Yageo"))
      (libsource (lib "") (part "Resistor_1"))
    )
    (comp (ref "R65")
      (value "100k")
      (footprint "CH0805R")
      (fields (field (name "MANUFACTURER") "Yageo") (field (name "COMPONENTKIND") "±1%"))
      (libsource (lib "") (part "Resistor_1"))
    )
    (comp (ref "R66")
      (value "1k")
      (footprint "CH0805R")
      (fields (field (name "MANUFACTURER") "Yageo"))
      (libsource (lib "Discrete") (part "Resistor"))
    )
    (comp (ref "R67")
      (value "1k")
      (footprint "CH0805R")
      (fields (field (name "MANUFACTURER") "Yageo"))
      (libsource (lib "") (part "Resistor_3"))
    )
    (comp (ref "R68")
      (value "18k")
      (footprint "CH0805R")
      (fields (field (name "MANUFACTURER") "Yageo"))
      (libsource (lib "") (part "Resistor_2"))
    )
    (comp (ref "R69")
      (value "10k")
      (footprint "RES: 3296W")
      (fields (field (name "MANUFACTURER") "Bourns Inc."))
      (libsource (lib "Discrete") (part "ADJ resistor"))
    )
    (comp (ref "R70")
      (value "10k")
      (footprint "CH0805R")
      (fields (field (name "MANUFACTURER") "Yageo") (field (name "COMPONENTKIND") "±1%"))
      (libsource (lib "Discrete") (part "Resistor"))
    )
    (comp (ref "R71")
      (value "24k")
      (footprint "CH0805R")
      (fields (field (name "MANUFACTURER") "Yageo") (field (name "COMPONENTKIND") "±1%"))
      (libsource (lib "") (part "Resistor_2"))
    )
    (comp (ref "R72")
      (value "51R")
      (footprint "CH0805R")
      (fields (field (name "MANUFACTURER") "Yageo"))
      (libsource (lib "") (part "Resistor_2"))
    )
    (comp (ref "R73")
      (value "1k")
      (footprint "CH0805R")
      (fields (field (name "MANUFACTURER") "Yageo"))
      (libsource (lib "") (part "Resistor_3"))
    )
    (comp (ref "R74")
      (value "10k")
      (footprint "CH0805R")
      (fields (field (name "MANUFACTURER") "Yageo"))
      (libsource (lib "") (part "Resistor_1"))
    )
    (comp (ref "R75")
      (value "0R2")
      (footprint "CH1206R")
      (fields (field (name "MANUFACTURER") "Yageo") (field (name "COMPONENTKIND") "±1%"))
      (libsource (lib "Discrete") (part "Resistor"))
    )
    (comp (ref "R76")
      (value "0R2")
      (footprint "CH1206R")
      (fields (field (name "MANUFACTURER") "Yageo") (field (name "COMPONENTKIND") "±1%"))
      (libsource (lib "") (part "Resistor_2"))
    )
    (comp (ref "R77")
      (value "0R2")
      (footprint "CH1206R")
      (fields (field (name "MANUFACTURER") "Yageo") (field (name "COMPONENTKIND") "±1%"))
      (libsource (lib "") (part "Resistor_2"))
    )
    (comp (ref "R78")
      (value "9k1")
      (footprint "CH0805R")
      (fields (field (name "MANUFACTURER") "Yageo") (field (name "COMPONENTKIND") "±1%"))
      (libsource (lib "") (part "Resistor_3"))
    )
    (comp (ref "R79")
      (value "4k7")
      (footprint "CH0805R")
      (fields (field (name "MANUFACTURER") "Yageo") (field (name "COMPONENTKIND") "±1%"))
      (libsource (lib "") (part "Resistor_3"))
    )
    (comp (ref "R80")
      (value "1k")
      (footprint "CH0805R")
      (fields (field (name "MANUFACTURER") "Yageo") (field (name "COMPONENTKIND") "±1%"))
      (libsource (lib "Discrete") (part "Resistor"))
    )
    (comp (ref "R81")
      (value "1k")
      (footprint "CH0805R")
      (fields (field (name "MANUFACTURER") "Yageo") (field (name "COMPONENTKIND") "±1%"))
      (libsource (lib "Discrete") (part "Resistor"))
    )
    (comp (ref "T1")
      (value "ETD59/31/22")
      (footprint "TRANS: ETD59/31/22")
      (description "Impulse")
      (fields (field (name "MANUFACTURER") "Epcos"))
      (libsource (lib "") (part "Push-Pull_1"))
    )
    (comp (ref "T2")
      (value "EFD20/10/7")
      (footprint "TRANS: EFD20/10/7")
      (description "Impulse")
      (fields (field (name "MANUFACTURER") "Ferroxcube"))
      (libsource (lib "Transformers") (part "Isolator"))
    )
    (comp (ref "T4")
      (value "ETD59/31/22")
      (footprint "TRANS: ETD59/31/22")
      (description "Impulse")
      (fields (field (name "MANUFACTURER") "Epcos"))
      (libsource (lib "Transformers") (part "Push-Pull"))
    )
    (comp (ref "U1")
      (value "LTV-817S")
      (footprint "4-SMD")
      (fields (field (name "MANUFACTURER") "Lite-On Inc."))
      (libsource (lib "Discrete") (part "Optoisolator"))
    )
    (comp (ref "U2")
      (value "LTV-817S")
      (footprint "4-SMD")
      (fields (field (name "MANUFACTURER") "Lite-On Inc."))
      (libsource (lib "Discrete") (part "Optoisolator"))
    )
    (comp (ref "VD1")
      (value "ESD5Z3.3T1G")
      (footprint "SOD523")
      (fields (field (name "MANUFACTURER") "ON Semiconductor"))
      (libsource (lib "Diods") (part "Diod Zener"))
    )
    (comp (ref "VD2")
      (value "SS24FL")
      (footprint "SOD123F")
      (fields (field (name "MANUFACTURER") "Fairchild/ON Semiconductor"))
      (libsource (lib "Diods") (part "Diod Schottky"))
    )
    (comp (ref "VD3")
      (value "SMBJ30A")
      (footprint "SMB")
      (fields (field (name "MANUFACTURER") "Fairchild/ON Semiconductor"))
      (libsource (lib "Diods") (part "Diod Zener"))
    )
    (comp (ref "VD4")
      (value "SMBJ30A")
      (footprint "SMB")
      (fields (field (name "MANUFACTURER") "Fairchild/ON Semiconductor"))
      (libsource (lib "Diods") (part "Diod Zener"))
    )
    (comp (ref "VD5")
      (value "SMBJ30A")
      (footprint "SMB")
      (fields (field (name "MANUFACTURER") "Fairchild/ON Semiconductor"))
      (libsource (lib "Diods") (part "Diod Zener"))
    )
    (comp (ref "VD6")
      (value "SMBJ30A")
      (footprint "SMB")
      (fields (field (name "MANUFACTURER") "Fairchild/ON Semiconductor"))
      (libsource (lib "Diods") (part "Diod Zener"))
    )
    (comp (ref "VD7")
      (value "SMBJ30A")
      (footprint "SMB")
      (fields (field (name "MANUFACTURER") "Fairchild/ON Semiconductor"))
      (libsource (lib "Diods") (part "Diod Zener"))
    )
    (comp (ref "VD8")
      (value "SMBJ30A")
      (footprint "SMB")
      (fields (field (name "MANUFACTURER") "Fairchild/ON Semiconductor"))
      (libsource (lib "Diods") (part "Diod Zener"))
    )
    (comp (ref "VD9")
      (value "SMBJ30A")
      (footprint "SMB")
      (fields (field (name "MANUFACTURER") "Fairchild/ON Semiconductor"))
      (libsource (lib "Diods") (part "Diod Zener"))
    )
    (comp (ref "VD10")
      (value "SMBJ30A")
      (footprint "SMB")
      (fields (field (name "MANUFACTURER") "Fairchild/ON Semiconductor"))
      (libsource (lib "Diods") (part "Diod Zener"))
    )
    (comp (ref "VD11")
      (value "SS24FL")
      (footprint "SOD123F")
      (fields (field (name "MANUFACTURER") "Fairchild/ON Semiconductor"))
      (libsource (lib "Diods") (part "Diod Schottky"))
    )
    (comp (ref "VD12")
      (value "SS24FL")
      (footprint "SOD123F")
      (fields (field (name "MANUFACTURER") "Fairchild/ON Semiconductor"))
      (libsource (lib "Diods") (part "Diod Schottky"))
    )
    (comp (ref "VD13")
      (value "SS24FL")
      (footprint "SOD123F")
      (fields (field (name "MANUFACTURER") "Fairchild/ON Semiconductor"))
      (libsource (lib "Diods") (part "Diod Schottky"))
    )
    (comp (ref "VD14")
      (value "SS24FL")
      (footprint "SOD123F")
      (fields (field (name "MANUFACTURER") "Fairchild/ON Semiconductor"))
      (libsource (lib "Diods") (part "Diod Schottky"))
    )
    (comp (ref "VD15")
      (value "SS24FL")
      (footprint "SOD123F")
      (fields (field (name "MANUFACTURER") "Fairchild/ON Semiconductor"))
      (libsource (lib "Diods") (part "Diod Schottky"))
    )
    (comp (ref "VD16")
      (value "SS24FL")
      (footprint "SOD123F")
      (fields (field (name "MANUFACTURER") "Fairchild/ON Semiconductor"))
      (libsource (lib "Diods") (part "Diod Schottky"))
    )
    (comp (ref "VD17")
      (value "SS24FL")
      (footprint "SOD123F")
      (fields (field (name "MANUFACTURER") "Fairchild/ON Semiconductor"))
      (libsource (lib "Diods") (part "Diod Schottky"))
    )
    (comp (ref "VD18")
      (value "SS24FL")
      (footprint "SOD123F")
      (fields (field (name "MANUFACTURER") "Fairchild/ON Semiconductor"))
      (libsource (lib "Diods") (part "Diod Schottky"))
    )
    (comp (ref "VD19")
      (value "SD15C-01FT")
      (footprint "SOD323")
      (fields (field (name "MANUFACTURER") "Littelfuse Inc."))
      (libsource (lib "Diods") (part "TVS-diod"))
    )
    (comp (ref "VD20")
      (value "SS24FL")
      (footprint "SOD123F")
      (fields (field (name "MANUFACTURER") "Fairchild/ON Semiconductor"))
      (libsource (lib "Diods") (part "Diod Schottky"))
    )
    (comp (ref "VD21")
      (value "SD15C")
      (footprint "SOD323")
      (fields (field (name "MANUFACTURER") "Littelfuse Inc."))
      (libsource (lib "Diods") (part "TVS-diod"))
    )
    (comp (ref "VD22")
      (value "SD15C")
      (footprint "SOD323")
      (fields (field (name "MANUFACTURER") "Littelfuse Inc."))
      (libsource (lib "Diods") (part "TVS-diod"))
    )
    (comp (ref "VD23")
      (value "SD15C")
      (footprint "SOD323")
      (fields (field (name "MANUFACTURER") "Littelfuse Inc."))
      (libsource (lib "Diods") (part "TVS-diod"))
    )
    (comp (ref "VD24")
      (value "SD15C")
      (footprint "SOD323")
      (fields (field (name "MANUFACTURER") "Littelfuse Inc."))
      (libsource (lib "Diods") (part "TVS-diod"))
    )
    (comp (ref "VD25")
      (value "SD15C")
      (footprint "SOD323")
      (fields (field (name "MANUFACTURER") "Littelfuse Inc."))
      (libsource (lib "Diods") (part "TVS-diod"))
    )
    (comp (ref "VD26")
      (value "SD15C")
      (footprint "SOD323")
      (fields (field (name "MANUFACTURER") "Littelfuse Inc."))
      (libsource (lib "Diods") (part "TVS-diod"))
    )
    (comp (ref "VD27")
      (value "SD15C")
      (footprint "SOD323")
      (fields (field (name "MANUFACTURER") "Littelfuse Inc."))
      (libsource (lib "Diods") (part "TVS-diod"))
    )
    (comp (ref "VD28")
      (value "SS24FL")
      (footprint "SOD123F")
      (fields (field (name "MANUFACTURER") "Fairchild/ON Semiconductor"))
      (libsource (lib "Diods") (part "Diod Schottky"))
    )
    (comp (ref "VD29")
      (value "SMBJ30A")
      (footprint "SMB")
      (fields (field (name "MANUFACTURER") "Fairchild/ON Semiconductor"))
      (libsource (lib "Diods") (part "Diod Zener"))
    )
    (comp (ref "VD30")
      (value "SMBJ30A")
      (footprint "SMB")
      (fields (field (name "MANUFACTURER") "Fairchild/ON Semiconductor"))
      (libsource (lib "Diods") (part "Diod Zener"))
    )
    (comp (ref "VD31")
      (value "SMBJ30A")
      (footprint "SMB")
      (fields (field (name "MANUFACTURER") "Fairchild/ON Semiconductor"))
      (libsource (lib "Diods") (part "Diod Zener"))
    )
    (comp (ref "VD32")
      (value "SMBJ30A")
      (footprint "SMB")
      (fields (field (name "MANUFACTURER") "Fairchild/ON Semiconductor"))
      (libsource (lib "Diods") (part "Diod Zener"))
    )
    (comp (ref "VD33")
      (value "SMBJ30A")
      (footprint "SMB")
      (fields (field (name "MANUFACTURER") "Fairchild/ON Semiconductor"))
      (libsource (lib "Diods") (part "Diod Zener"))
    )
    (comp (ref "VD34")
      (value "SMBJ30A")
      (footprint "SMB")
      (fields (field (name "MANUFACTURER") "Fairchild/ON Semiconductor"))
      (libsource (lib "Diods") (part "Diod Zener"))
    )
    (comp (ref "VD35")
      (value "SMBJ30A")
      (footprint "SMB")
      (fields (field (name "MANUFACTURER") "Fairchild/ON Semiconductor"))
      (libsource (lib "Diods") (part "Diod Zener"))
    )
    (comp (ref "VD36")
      (value "SMBJ30A")
      (footprint "SMB")
      (fields (field (name "MANUFACTURER") "Fairchild/ON Semiconductor"))
      (libsource (lib "Diods") (part "Diod Zener"))
    )
    (comp (ref "VD37")
      (value "SS24FL")
      (footprint "SOD123F")
      (fields (field (name "MANUFACTURER") "Fairchild/ON Semiconductor"))
      (libsource (lib "Diods") (part "Diod Schottky"))
    )
    (comp (ref "VD38")
      (value "SS24FL")
      (footprint "SOD123F")
      (fields (field (name "MANUFACTURER") "Fairchild/ON Semiconductor"))
      (libsource (lib "Diods") (part "Diod Schottky"))
    )
    (comp (ref "VD39")
      (value "SS24FL")
      (footprint "SOD123F")
      (fields (field (name "MANUFACTURER") "Fairchild/ON Semiconductor"))
      (libsource (lib "Diods") (part "Diod Schottky"))
    )
    (comp (ref "VD40")
      (value "SS24FL")
      (footprint "SOD123F")
      (fields (field (name "MANUFACTURER") "Fairchild/ON Semiconductor"))
      (libsource (lib "Diods") (part "Diod Schottky"))
    )
    (comp (ref "VD41")
      (value "SS24FL")
      (footprint "SOD123F")
      (fields (field (name "MANUFACTURER") "Fairchild/ON Semiconductor"))
      (libsource (lib "Diods") (part "Diod Schottky"))
    )
    (comp (ref "VD42")
      (value "SS24FL")
      (footprint "SOD123F")
      (fields (field (name "MANUFACTURER") "Fairchild/ON Semiconductor"))
      (libsource (lib "Diods") (part "Diod Schottky"))
    )
    (comp (ref "VD43")
      (value "SS24FL")
      (footprint "SOD123F")
      (fields (field (name "MANUFACTURER") "Fairchild/ON Semiconductor"))
      (libsource (lib "Diods") (part "Diod Schottky"))
    )
    (comp (ref "VD44")
      (value "SS24FL")
      (footprint "SOD123F")
      (fields (field (name "MANUFACTURER") "Fairchild/ON Semiconductor"))
      (libsource (lib "Diods") (part "Diod Schottky"))
    )
    (comp (ref "VD45")
      (value "SD15C-01FT")
      (footprint "SOD323")
      (fields (field (name "MANUFACTURER") "Littelfuse Inc."))
      (libsource (lib "Diods") (part "TVS-diod"))
    )
    (comp (ref "VD46")
      (value "SS24FL")
      (footprint "SOD123F")
      (fields (field (name "MANUFACTURER") "Fairchild/ON Semiconductor"))
      (libsource (lib "Diods") (part "Diod Schottky"))
    )
    (comp (ref "VD47")
      (value "SD15C")
      (footprint "SOD323")
      (fields (field (name "MANUFACTURER") "Littelfuse Inc."))
      (libsource (lib "Diods") (part "TVS-diod"))
    )
    (comp (ref "VD48")
      (value "SD15C")
      (footprint "SOD323")
      (fields (field (name "MANUFACTURER") "Littelfuse Inc."))
      (libsource (lib "Diods") (part "TVS-diod"))
    )
    (comp (ref "VD49")
      (value "SD15C")
      (footprint "SOD323")
      (fields (field (name "MANUFACTURER") "Littelfuse Inc."))
      (libsource (lib "Diods") (part "TVS-diod"))
    )
    (comp (ref "VD50")
      (value "SD15C")
      (footprint "SOD323")
      (fields (field (name "MANUFACTURER") "Littelfuse Inc."))
      (libsource (lib "Diods") (part "TVS-diod"))
    )
    (comp (ref "VD51")
      (value "SD15C")
      (footprint "SOD323")
      (fields (field (name "MANUFACTURER") "Littelfuse Inc."))
      (libsource (lib "Diods") (part "TVS-diod"))
    )
    (comp (ref "VD52")
      (value "SD15C")
      (footprint "SOD323")
      (fields (field (name "MANUFACTURER") "Littelfuse Inc."))
      (libsource (lib "Diods") (part "TVS-diod"))
    )
    (comp (ref "VD53")
      (value "SD15C")
      (footprint "SOD323")
      (fields (field (name "MANUFACTURER") "Littelfuse Inc."))
      (libsource (lib "Diods") (part "TVS-diod"))
    )
    (comp (ref "VD54")
      (value "HFA15TB60PBF")
      (footprint "TO220-2")
      (fields (field (name "MANUFACTURER") "Infineon Technologies"))
      (libsource (lib "Diods") (part "Diod"))
    )
    (comp (ref "VD55")
      (value "HFA15TB60PBF")
      (footprint "TO220-2")
      (fields (field (name "MANUFACTURER") "Infineon Technologies"))
      (libsource (lib "Diods") (part "Diod"))
    )
    (comp (ref "VD56")
      (value "SS26T3G")
      (footprint "SMB")
      (fields (field (name "MANUFACTURER") "ON Semiconductor"))
      (libsource (lib "Diods") (part "Diod Schottky"))
    )
    (comp (ref "VD57")
      (value "TL431AIDBZR")
      (footprint "SOT23_132")
      (fields (field (name "MANUFACTURER") "Texas Instruments"))
      (libsource (lib "Diods") (part "Program Zener"))
    )
    (comp (ref "VD58")
      (value "TL431AIDBZR")
      (footprint "SOT23_132")
      (fields (field (name "MANUFACTURER") "Texas Instruments"))
      (libsource (lib "Diods") (part "Program Zener"))
    )
    (comp (ref "VD59")
      (value "SS26T3G")
      (footprint "SMB")
      (fields (field (name "MANUFACTURER") "ON Semiconductor"))
      (libsource (lib "Diods") (part "Diod Schottky"))
    )
    (comp (ref "VD60")
      (value "HFA15TB60PBF")
      (footprint "TO220-2")
      (fields (field (name "MANUFACTURER") "Infineon Technologies"))
      (libsource (lib "Diods") (part "Diod"))
    )
    (comp (ref "VD61")
      (value "HFA15TB60PBF")
      (footprint "TO220-2")
      (fields (field (name "MANUFACTURER") "Infineon Technologies"))
      (libsource (lib "Diods") (part "Diod"))
    )
    (comp (ref "VD62")
      (value "SS24FL")
      (footprint "SOD123F")
      (fields (field (name "MANUFACTURER") "Fairchild/ON Semiconductor"))
      (libsource (lib "Diods") (part "Diod Schottky"))
    )
    (comp (ref "VD63")
      (value "SD15C-01FT")
      (footprint "SOD323")
      (fields (field (name "MANUFACTURER") "Littelfuse Inc."))
      (libsource (lib "Diods") (part "TVS-diod"))
    )
    (comp (ref "VD64")
      (value "SS26T3G")
      (footprint "SMB")
      (fields (field (name "MANUFACTURER") "ON Semiconductor"))
      (libsource (lib "Diods") (part "Diod Schottky"))
    )
    (comp (ref "VD65")
      (value "SS26T3G")
      (footprint "SMB")
      (fields (field (name "MANUFACTURER") "ON Semiconductor"))
      (libsource (lib "Diods") (part "Diod Schottky"))
    )
    (comp (ref "VT1")
      (value "IPP093N06N3")
      (footprint "TO220_123")
      (description "Mosfet")
      (fields (field (name "MANUFACTURER") "Infineon Technologies"))
      (libsource (lib "Transistor") (part "N-chanel"))
    )
    (comp (ref "VT2")
      (value "IPP093N06N3")
      (footprint "TO220_123")
      (description "Mosfet")
      (fields (field (name "MANUFACTURER") "Infineon Technologies"))
      (libsource (lib "Transistor") (part "N-chanel"))
    )
    (comp (ref "VT3")
      (value "IPP093N06N3")
      (footprint "TO220_123")
      (description "Mosfet")
      (fields (field (name "MANUFACTURER") "Infineon Technologies"))
      (libsource (lib "Transistor") (part "N-chanel"))
    )
    (comp (ref "VT4")
      (value "IPP093N06N3")
      (footprint "TO220_123")
      (description "Mosfet")
      (fields (field (name "MANUFACTURER") "Infineon Technologies"))
      (libsource (lib "Transistor") (part "N-chanel"))
    )
    (comp (ref "VT5")
      (value "IPP093N06N3")
      (footprint "TO220_123")
      (description "Mosfet")
      (fields (field (name "MANUFACTURER") "Infineon Technologies"))
      (libsource (lib "Transistor") (part "N-chanel"))
    )
    (comp (ref "VT6")
      (value "IPP093N06N3")
      (footprint "TO220_123")
      (description "Mosfet")
      (fields (field (name "MANUFACTURER") "Infineon Technologies"))
      (libsource (lib "Transistor") (part "N-chanel"))
    )
    (comp (ref "VT7")
      (value "IPP093N06N3")
      (footprint "TO220_123")
      (description "Mosfet")
      (fields (field (name "MANUFACTURER") "Infineon Technologies"))
      (libsource (lib "Transistor") (part "N-chanel"))
    )
    (comp (ref "VT8")
      (value "IPP093N06N3")
      (footprint "TO220_123")
      (description "Mosfet")
      (fields (field (name "MANUFACTURER") "Infineon Technologies"))
      (libsource (lib "Transistor") (part "N-chanel"))
    )
    (comp (ref "VT9")
      (value "IPP093N06N3")
      (footprint "TO220_123")
      (description "Mosfet")
      (fields (field (name "MANUFACTURER") "Infineon Technologies"))
      (libsource (lib "Transistor") (part "N-chanel"))
    )
    (comp (ref "VT10")
      (value "IPP093N06N3")
      (footprint "TO220_123")
      (description "Mosfet")
      (fields (field (name "MANUFACTURER") "Infineon Technologies"))
      (libsource (lib "Transistor") (part "N-chanel"))
    )
    (comp (ref "VT11")
      (value "IPP093N06N3")
      (footprint "TO220_123")
      (description "Mosfet")
      (fields (field (name "MANUFACTURER") "Infineon Technologies"))
      (libsource (lib "Transistor") (part "N-chanel"))
    )
    (comp (ref "VT12")
      (value "IPP093N06N3")
      (footprint "TO220_123")
      (description "Mosfet")
      (fields (field (name "MANUFACTURER") "Infineon Technologies"))
      (libsource (lib "Transistor") (part "N-chanel"))
    )
    (comp (ref "VT13")
      (value "IPP093N06N3")
      (footprint "TO220_123")
      (description "Mosfet")
      (fields (field (name "MANUFACTURER") "Infineon Technologies"))
      (libsource (lib "Transistor") (part "N-chanel"))
    )
    (comp (ref "VT14")
      (value "IPP093N06N3")
      (footprint "TO220_123")
      (description "Mosfet")
      (fields (field (name "MANUFACTURER") "Infineon Technologies"))
      (libsource (lib "Transistor") (part "N-chanel"))
    )
    (comp (ref "VT15")
      (value "IPP093N06N3")
      (footprint "TO220_123")
      (description "Mosfet")
      (fields (field (name "MANUFACTURER") "Infineon Technologies"))
      (libsource (lib "Transistor") (part "N-chanel"))
    )
    (comp (ref "VT16")
      (value "IPP093N06N3")
      (footprint "TO220_123")
      (description "Mosfet")
      (fields (field (name "MANUFACTURER") "Infineon Technologies"))
      (libsource (lib "Transistor") (part "N-chanel"))
    )
    (comp (ref "VT17")
      (value "IRF7853PBF")
      (footprint "TRANS: SO-8")
      (description "Mosfet")
      (fields (field (name "MANUFACTURER") "Infineon Technologies"))
      (libsource (lib "Transistor") (part "N-chanel"))
    )
    (comp (ref "X1")
      (value "\"Вход +24В\"")
      (footprint "CON: 7461383")
      (fields (field (name "MANUFACTURER") "Wurth Electronics Inc."))
      (libsource (lib "Connectors") (part "1-Connector"))
    )
    (comp (ref "X2")
      (value "\"Вход -24В\"")
      (footprint "CON: 7461383")
      (fields (field (name "MANUFACTURER") "Wurth Electronics Inc."))
      (libsource (lib "Connectors") (part "1-Connector"))
    )
  )
  (nets
    (net (code "1") (name "/ADC_CUR_IN") (class "Default")
      (node (ref "D3") (pin "1") (pinfunction "OUT_1") (pintype "output"))
      (node (ref "R2") (pin "2") (pinfunction "2_2") (pintype "passive"))
    )
    (net (code "2") (name "/ADC_VCC_IN") (class "Default")
      (node (ref "D2") (pin "1") (pinfunction "OUT_1") (pintype "output"))
      (node (ref "R1") (pin "2") (pinfunction "2_2") (pintype "passive"))
    )
    (net (code "3") (name "/CH1_ENABLE") (class "Default")
      (node (ref "R13") (pin "2") (pinfunction "2_2") (pintype "passive"))
    )
    (net (code "4") (name "/CH2_ENABLE") (class "Default")
      (node (ref "R39") (pin "2") (pinfunction "2_2") (pintype "passive"))
    )
    (net (code "5") (name "/PWM3_CH3") (class "Default")
      (node (ref "R23") (pin "2") (pinfunction "2_2") (pintype "passive"))
    )
    (net (code "6") (name "/PWM3_CH4") (class "Default")
      (node (ref "R49") (pin "2") (pinfunction "2_2") (pintype "passive"))
    )
    (net (code "7") (name "GND") (class "Default")
      (node (ref "C10") (pin "2") (pinfunction "2_2") (pintype "power_in"))
      (node (ref "C11") (pin "2") (pinfunction "2_2") (pintype "power_in"))
      (node (ref "C12") (pin "2") (pinfunction "2_2") (pintype "power_in"))
      (node (ref "C13") (pin "2") (pinfunction "2_2") (pintype "power_in"))
      (node (ref "C14") (pin "2") (pinfunction "2_2") (pintype "power_in"))
      (node (ref "C15") (pin "2") (pinfunction "2_2") (pintype "power_in"))
      (node (ref "C16") (pin "2") (pinfunction "2_2") (pintype "power_in"))
      (node (ref "C17") (pin "2") (pinfunction "2_2") (pintype "power_in"))
      (node (ref "C18") (pin "2") (pinfunction "2_2") (pintype "power_in"))
      (node (ref "C19") (pin "2") (pinfunction "2_2") (pintype "power_in"))
      (node (ref "C2") (pin "2") (pinfunction "2_2") (pintype "power_in"))
      (node (ref "C20") (pin "2") (pinfunction "2_2") (pintype "power_in"))
      (node (ref "C21") (pin "2") (pinfunction "2_2") (pintype "power_in"))
      (node (ref "C22") (pin "1") (pinfunction "1_1") (pintype "power_in"))
      (node (ref "C23") (pin "2") (pinfunction "2_2") (pintype "power_in"))
      (node (ref "C24") (pin "1") (pinfunction "1_1") (pintype "power_in"))
      (node (ref "C25") (pin "1") (pinfunction "1_1") (pintype "power_in"))
      (node (ref "C26") (pin "2") (pinfunction "2_2") (pintype "power_in"))
      (node (ref "C27") (pin "1") (pinfunction "1_1") (pintype "power_in"))
      (node (ref "C28") (pin "2") (pinfunction "2_2") (pintype "power_in"))
      (node (ref "C29") (pin "1") (pinfunction "1_1") (pintype "power_in"))
      (node (ref "C3") (pin "2") (pinfunction "2_2") (pintype "power_in"))
      (node (ref "C30") (pin "2") (pinfunction "2_2") (pintype "power_in"))
      (node (ref "C31") (pin "1") (pinfunction "1_1") (pintype "power_in"))
      (node (ref "C32") (pin "1") (pinfunction "1_1") (pintype "power_in"))
      (node (ref "C33") (pin "2") (pinfunction "2_2") (pintype "power_in"))
      (node (ref "C34") (pin "2") (pinfunction "2_2") (pintype "power_in"))
      (node (ref "C35") (pin "2") (pinfunction "2_2") (pintype "power_in"))
      (node (ref "C36") (pin "1") (pinfunction "1_1") (pintype "power_in"))
      (node (ref "C37") (pin "2") (pinfunction "2_2") (pintype "power_in"))
      (node (ref "C38") (pin "1") (pinfunction "1_1") (pintype "power_in"))
      (node (ref "C39") (pin "2") (pinfunction "2_2") (pintype "power_in"))
      (node (ref "C4") (pin "2") (pinfunction "2_2") (pintype "power_in"))
      (node (ref "C40") (pin "1") (pinfunction "1_1") (pintype "power_in"))
      (node (ref "C41") (pin "1") (pinfunction "1_1") (pintype "power_in"))
      (node (ref "C42") (pin "2") (pinfunction "2_2") (pintype "power_in"))
      (node (ref "C43") (pin "2") (pinfunction "2_2") (pintype "power_in"))
      (node (ref "C5") (pin "2") (pinfunction "2_2") (pintype "power_in"))
      (node (ref "C56") (pin "1") (pinfunction "1_1") (pintype "power_in"))
      (node (ref "C57") (pin "1") (pinfunction "1_1") (pintype "power_in"))
      (node (ref "C58") (pin "2") (pinfunction "2_2") (pintype "power_in"))
      (node (ref "C59") (pin "2") (pinfunction "2_2") (pintype "power_in"))
      (node (ref "C6") (pin "2") (pinfunction "2_2") (pintype "power_in"))
      (node (ref "C62") (pin "1") (pinfunction "1_1") (pintype "power_in"))
      (node (ref "C63") (pin "1") (pinfunction "1_1") (pintype "power_in"))
      (node (ref "C64") (pin "1") (pinfunction "1_1") (pintype "power_in"))
      (node (ref "C65") (pin "1") (pinfunction "1_1") (pintype "power_in"))
      (node (ref "C66") (pin "1") (pinfunction "1_1") (pintype "power_in"))
      (node (ref "C67") (pin "2") (pinfunction "2_2") (pintype "power_in"))
      (node (ref "C68") (pin "2") (pinfunction "2_2") (pintype "power_in"))
      (node (ref "C69") (pin "1") (pinfunction "1_1") (pintype "power_in"))
      (node (ref "C7") (pin "2") (pinfunction "2_2") (pintype "power_in"))
      (node (ref "C70") (pin "1") (pinfunction "1_1") (pintype "power_in"))
      (node (ref "C71") (pin "1") (pinfunction "1_1") (pintype "power_in"))
      (node (ref "C72") (pin "1") (pinfunction "1_1") (pintype "power_in"))
      (node (ref "C73") (pin "1") (pinfunction "1_1") (pintype "power_in"))
      (node (ref "C74") (pin "2") (pinfunction "2_2") (pintype "power_in"))
      (node (ref "C75") (pin "1") (pinfunction "1_1") (pintype "power_in"))
      (node (ref "C76") (pin "1") (pinfunction "1_1") (pintype "power_in"))
      (node (ref "C77") (pin "1") (pinfunction "1_1") (pintype "power_in"))
      (node (ref "C78") (pin "1") (pinfunction "1_1") (pintype "power_in"))
      (node (ref "C79") (pin "1") (pinfunction "1_1") (pintype "power_in"))
      (node (ref "C8") (pin "2") (pinfunction "2_2") (pintype "power_in"))
      (node (ref "C80") (pin "1") (pinfunction "1_1") (pintype "power_in"))
      (node (ref "C9") (pin "2") (pinfunction "2_2") (pintype "power_in"))
      (node (ref "D1") (pin "2") (pinfunction "GND_2") (pintype "passive"))
      (node (ref "D10") (pin "4") (pinfunction "COM_4") (pintype "power_in"))
      (node (ref "D11") (pin "4") (pinfunction "AGND_4") (pintype "passive"))
      (node (ref "D11") (pin "5") (pinfunction "PGND_5") (pintype "passive"))
      (node (ref "D12") (pin "2") (pinfunction "VFB_2") (pintype "passive"))
      (node (ref "D12") (pin "5") (pinfunction "GND_5") (pintype "passive"))
      (node (ref "D14") (pin "4") (pinfunction "GND_4") (pintype "passive"))
      (node (ref "D15") (pin "4") (pinfunction "GND_4") (pintype "passive"))
      (node (ref "D16") (pin "1") (pinfunction "GND_1") (pintype "passive"))
      (node (ref "D17") (pin "1") (pinfunction "GND_1") (pintype "passive"))
      (node (ref "D2") (pin "2") (pinfunction "GND_2") (pintype "power_in"))
      (node (ref "D3") (pin "2") (pinfunction "GND_2") (pintype "power_in"))
      (node (ref "D4") (pin "2") (pinfunction "GND_2") (pintype "power_in"))
      (node (ref "D5") (pin "2") (pinfunction "GND_2") (pintype "power_in"))
      (node (ref "D6") (pin "4") (pinfunction "COM_4") (pintype "power_in"))
      (node (ref "D7") (pin "4") (pinfunction "AGND_4") (pintype "passive"))
      (node (ref "D7") (pin "5") (pinfunction "PGND_5") (pintype "passive"))
      (node (ref "D8") (pin "2") (pinfunction "GND_2") (pintype "power_in"))
      (node (ref "D9") (pin "2") (pinfunction "GND_2") (pintype "power_in"))
      (node (ref "R11") (pin "2") (pinfunction "2_2") (pintype "passive"))
      (node (ref "R12") (pin "2") (pinfunction "2_2") (pintype "passive"))
      (node (ref "R24") (pin "1") (pinfunction "1_1") (pintype "passive"))
      (node (ref "R25") (pin "1") (pinfunction "1_1") (pintype "passive"))
      (node (ref "R26") (pin "1") (pinfunction "1_1") (pintype "passive"))
      (node (ref "R27") (pin "1") (pinfunction "1_1") (pintype "passive"))
      (node (ref "R28") (pin "1") (pinfunction "1_1") (pintype "passive"))
      (node (ref "R29") (pin "1") (pinfunction "1_1") (pintype "passive"))
      (node (ref "R30") (pin "1") (pinfunction "1_1") (pintype "passive"))
      (node (ref "R31") (pin "1") (pinfunction "1_1") (pintype "passive"))
      (node (ref "R32") (pin "1") (pinfunction "1_1") (pintype "passive"))
      (node (ref "R37") (pin "2") (pinfunction "2_2") (pintype "passive"))
      (node (ref "R38") (pin "2") (pinfunction "2_2") (pintype "passive"))
      (node (ref "R50") (pin "1") (pinfunction "1_1") (pintype "passive"))
      (node (ref "R51") (pin "1") (pinfunction "1_1") (pintype "passive"))
      (node (ref "R52") (pin "1") (pinfunction "1_1") (pintype "passive"))
      (node (ref "R53") (pin "1") (pinfunction "1_1") (pintype "passive"))
      (node (ref "R54") (pin "1") (pinfunction "1_1") (pintype "passive"))
      (node (ref "R55") (pin "1") (pinfunction "1_1") (pintype "passive"))
      (node (ref "R56") (pin "1") (pinfunction "1_1") (pintype "passive"))
      (node (ref "R57") (pin "1") (pinfunction "1_1") (pintype "passive"))
      (node (ref "R58") (pin "1") (pinfunction "1_1") (pintype "passive"))
      (node (ref "R6") (pin "2") (pinfunction "2_2") (pintype "passive"))
      (node (ref "R74") (pin "1") (pinfunction "1_1") (pintype "passive"))
      (node (ref "R75") (pin "2") (pinfunction "2_2") (pintype "passive"))
      (node (ref "R80") (pin "2") (pinfunction "2_2") (pintype "passive"))
      (node (ref "R81") (pin "2") (pinfunction "2_2") (pintype "passive"))
      (node (ref "U1") (pin "3") (pinfunction "E_3") (pintype "passive"))
      (node (ref "VD1") (pin "1") (pinfunction "A_1") (pintype "passive"))
      (node (ref "VD10") (pin "1") (pinfunction "A_1") (pintype "passive"))
      (node (ref "VD19") (pin "1") (pinfunction "A_1") (pintype "passive"))
      (node (ref "VD20") (pin "1") (pinfunction "1_1") (pintype "passive"))
      (node (ref "VD21") (pin "1") (pinfunction "A_1") (pintype "passive"))
      (node (ref "VD22") (pin "1") (pinfunction "A_1") (pintype "passive"))
      (node (ref "VD23") (pin "1") (pinfunction "A_1") (pintype "passive"))
      (node (ref "VD24") (pin "1") (pinfunction "A_1") (pintype "passive"))
      (node (ref "VD25") (pin "1") (pinfunction "A_1") (pintype "passive"))
      (node (ref "VD26") (pin "1") (pinfunction "A_1") (pintype "passive"))
      (node (ref "VD27") (pin "1") (pinfunction "A_1") (pintype "passive"))
      (node (ref "VD29") (pin "1") (pinfunction "A_1") (pintype "passive"))
      (node (ref "VD3") (pin "1") (pinfunction "A_1") (pintype "passive"))
      (node (ref "VD30") (pin "1") (pinfunction "A_1") (pintype "passive"))
      (node (ref "VD31") (pin "1") (pinfunction "A_1") (pintype "passive"))
      (node (ref "VD32") (pin "1") (pinfunction "A_1") (pintype "passive"))
      (node (ref "VD33") (pin "1") (pinfunction "A_1") (pintype "passive"))
      (node (ref "VD34") (pin "1") (pinfunction "A_1") (pintype "passive"))
      (node (ref "VD35") (pin "1") (pinfunction "A_1") (pintype "passive"))
      (node (ref "VD36") (pin "1") (pinfunction "A_1") (pintype "passive"))
      (node (ref "VD4") (pin "1") (pinfunction "A_1") (pintype "passive"))
      (node (ref "VD45") (pin "1") (pinfunction "A_1") (pintype "passive"))
      (node (ref "VD46") (pin "1") (pinfunction "1_1") (pintype "passive"))
      (node (ref "VD47") (pin "1") (pinfunction "A_1") (pintype "passive"))
      (node (ref "VD48") (pin "1") (pinfunction "A_1") (pintype "passive"))
      (node (ref "VD49") (pin "1") (pinfunction "A_1") (pintype "passive"))
      (node (ref "VD5") (pin "1") (pinfunction "A_1") (pintype "passive"))
      (node (ref "VD50") (pin "1") (pinfunction "A_1") (pintype "passive"))
      (node (ref "VD51") (pin "1") (pinfunction "A_1") (pintype "passive"))
      (node (ref "VD52") (pin "1") (pinfunction "A_1") (pintype "passive"))
      (node (ref "VD53") (pin "1") (pinfunction "A_1") (pintype "passive"))
      (node (ref "VD6") (pin "1") (pinfunction "A_1") (pintype "passive"))
      (node (ref "VD63") (pin "1") (pinfunction "A_1") (pintype "passive"))
      (node (ref "VD64") (pin "1") (pinfunction "1_1") (pintype "passive"))
      (node (ref "VD65") (pin "1") (pinfunction "1_1") (pintype "passive"))
      (node (ref "VD7") (pin "1") (pinfunction "A_1") (pintype "passive"))
      (node (ref "VD8") (pin "1") (pinfunction "A_1") (pintype "passive"))
      (node (ref "VD9") (pin "1") (pinfunction "A_1") (pintype "passive"))
      (node (ref "VT1") (pin "3") (pinfunction "S_3") (pintype "passive"))
      (node (ref "VT10") (pin "3") (pinfunction "S_3") (pintype "passive"))
      (node (ref "VT11") (pin "3") (pinfunction "S_3") (pintype "passive"))
      (node (ref "VT12") (pin "3") (pinfunction "S_3") (pintype "passive"))
      (node (ref "VT13") (pin "3") (pinfunction "S_3") (pintype "passive"))
      (node (ref "VT14") (pin "3") (pinfunction "S_3") (pintype "passive"))
      (node (ref "VT15") (pin "3") (pinfunction "S_3") (pintype "passive"))
      (node (ref "VT16") (pin "3") (pinfunction "S_3") (pintype "passive"))
      (node (ref "VT2") (pin "3") (pinfunction "S_3") (pintype "passive"))
      (node (ref "VT3") (pin "3") (pinfunction "S_3") (pintype "passive"))
      (node (ref "VT4") (pin "3") (pinfunction "S_3") (pintype "passive"))
      (node (ref "VT5") (pin "3") (pinfunction "S_3") (pintype "passive"))
      (node (ref "VT6") (pin "3") (pinfunction "S_3") (pintype "passive"))
      (node (ref "VT7") (pin "3") (pinfunction "S_3") (pintype "passive"))
      (node (ref "VT8") (pin "3") (pinfunction "S_3") (pintype "passive"))
      (node (ref "VT9") (pin "3") (pinfunction "S_3") (pintype "passive"))
      (node (ref "X2") (pin "1") (pinfunction "1_1") (pintype "passive"))
    )
    (net (code "8") (name "GND2") (class "Default")
      (node (ref "C48") (pin "2") (pinfunction "2_2") (pintype "power_in"))
      (node (ref "C49") (pin "2") (pinfunction "2_2") (pintype "power_in"))
      (node (ref "C50") (pin "2") (pinfunction "2_2") (pintype "power_in"))
      (node (ref "C51") (pin "2") (pinfunction "2_2") (pintype "power_in"))
      (node (ref "C52") (pin "2") (pinfunction "2_2") (pintype "power_in"))
      (node (ref "C53") (pin "1") (pinfunction "1_1") (pintype "power_in"))
      (node (ref "C54") (pin "2") (pinfunction "2_2") (pintype "power_in"))
      (node (ref "C55") (pin "1") (pinfunction "1_1") (pintype "power_in"))
      (node (ref "C60") (pin "1") (pinfunction "1_1") (pintype "power_in"))
      (node (ref "C61") (pin "1") (pinfunction "1_1") (pintype "power_in"))
      (node (ref "C62") (pin "2") (pinfunction "2_2") (pintype "power_in"))
      (node (ref "D13") (pin "1") (pinfunction "GND_1") (pintype "passive"))
      (node (ref "R69") (pin "1") (pinfunction "1_1") (pintype "passive"))
      (node (ref "R69") (pin "2") (pinfunction "2_2") (pintype "passive"))
      (node (ref "R70") (pin "2") (pinfunction "2_2") (pintype "passive"))
      (node (ref "R71") (pin "2") (pinfunction "2_2") (pintype "passive"))
      (node (ref "T2") (pin "3") (pinfunction "3_3") (pintype "power_in"))
      (node (ref "VD57") (pin "3") (pinfunction "3_3") (pintype "power_in"))
      (node (ref "VD58") (pin "3") (pinfunction "3_3") (pintype "power_in"))
      (node (ref "VD60") (pin "1") (pinfunction "1_1") (pintype "passive"))
      (node (ref "VD61") (pin "1") (pinfunction "1_1") (pintype "passive"))
    )
    (net (code "9") (name "Net-(C44-Pad1)") (class "Default")
      (node (ref "C44") (pin "1") (pinfunction "1_1") (pintype "power_in"))
      (node (ref "C46") (pin "1") (pinfunction "1_1") (pintype "power_in"))
      (node (ref "R65") (pin "2") (pinfunction "2_2") (pintype "passive"))
      (node (ref "R71") (pin "1") (pinfunction "1_1") (pintype "passive"))
      (node (ref "VD58") (pin "2") (pinfunction "2_2") (pintype "power_in"))
    )
    (net (code "10") (name "Net-(C44-Pad2)") (class "Default")
      (node (ref "C44") (pin "2") (pinfunction "2_2") (pintype "power_in"))
      (node (ref "R66") (pin "2") (pinfunction "2_2") (pintype "passive"))
    )
    (net (code "11") (name "Net-(C45-Pad1)") (class "Default")
      (node (ref "C45") (pin "1") (pinfunction "1_1") (pintype "power_in"))
      (node (ref "C47") (pin "1") (pinfunction "1_1") (pintype "power_in"))
      (node (ref "R63") (pin "2") (pinfunction "2_2") (pintype "passive"))
      (node (ref "R69") (pin "3") (pinfunction "3_3") (pintype "passive"))
      (node (ref "R70") (pin "1") (pinfunction "1_1") (pintype "passive"))
      (node (ref "VD57") (pin "2") (pinfunction "2_2") (pintype "power_in"))
    )
    (net (code "12") (name "Net-(C45-Pad2)") (class "Default")
      (node (ref "C45") (pin "2") (pinfunction "2_2") (pintype "power_in"))
      (node (ref "R67") (pin "2") (pinfunction "2_2") (pintype "passive"))
    )
    (net (code "13") (name "Net-(C52-Pad1)") (class "Default")
      (node (ref "C52") (pin "1") (pinfunction "1_1") (pintype "power_in"))
      (node (ref "C53") (pin "2") (pinfunction "2_2") (pintype "power_in"))
      (node (ref "FB1") (pin "2") (pinfunction "2_2") (pintype "passive"))
      (node (ref "VD59") (pin "2") (pinfunction "2_2") (pintype "passive"))
    )
    (net (code "14") (name "Net-(C75-Pad2)") (class "Default")
      (node (ref "C75") (pin "2") (pinfunction "2_2") (pintype "power_in"))
      (node (ref "C76") (pin "2") (pinfunction "2_2") (pintype "power_in"))
      (node (ref "C77") (pin "2") (pinfunction "2_2") (pintype "power_in"))
      (node (ref "FB2") (pin "2") (pinfunction "2_2") (pintype "passive"))
      (node (ref "FB3") (pin "2") (pinfunction "2_2") (pintype "passive"))
      (node (ref "L3") (pin "1") (pinfunction "1_1") (pintype "passive"))
      (node (ref "R79") (pin "2") (pinfunction "2_2") (pintype "passive"))
    )
    (net (code "15") (name "Net-(D1-IP+)") (class "Default")
      (node (ref "C1") (pin "1") (pinfunction "1_1") (pintype "power_in"))
      (node (ref "C10") (pin "1") (pinfunction "1_1") (pintype "power_in"))
      (node (ref "C11") (pin "1") (pinfunction "1_1") (pintype "power_in"))
      (node (ref "C12") (pin "1") (pinfunction "1_1") (pintype "power_in"))
      (node (ref "C13") (pin "1") (pinfunction "1_1") (pintype "power_in"))
      (node (ref "C14") (pin "1") (pinfunction "1_1") (pintype "power_in"))
      (node (ref "C15") (pin "1") (pinfunction "1_1") (pintype "power_in"))
      (node (ref "C16") (pin "1") (pinfunction "1_1") (pintype "power_in"))
      (node (ref "C17") (pin "1") (pinfunction "1_1") (pintype "power_in"))
      (node (ref "C18") (pin "1") (pinfunction "1_1") (pintype "power_in"))
      (node (ref "C19") (pin "1") (pinfunction "1_1") (pintype "power_in"))
      (node (ref "C2") (pin "1") (pinfunction "1_1") (pintype "power_in"))
      (node (ref "C20") (pin "1") (pinfunction "1_1") (pintype "power_in"))
      (node (ref "C21") (pin "1") (pinfunction "1_1") (pintype "power_in"))
      (node (ref "C3") (pin "1") (pinfunction "1_1") (pintype "power_in"))
      (node (ref "C4") (pin "1") (pinfunction "1_1") (pintype "power_in"))
      (node (ref "C5") (pin "1") (pinfunction "1_1") (pintype "power_in"))
      (node (ref "C6") (pin "1") (pinfunction "1_1") (pintype "power_in"))
      (node (ref "C7") (pin "1") (pinfunction "1_1") (pintype "power_in"))
      (node (ref "C8") (pin "1") (pinfunction "1_1") (pintype "power_in"))
      (node (ref "C9") (pin "1") (pinfunction "1_1") (pintype "power_in"))
      (node (ref "D1") (pin "4") (pinfunction "IP+_4") (pintype "passive"))
      (node (ref "R3") (pin "1") (pinfunction "1_1") (pintype "passive"))
      (node (ref "X1") (pin "1") (pinfunction "1_1") (pintype "passive"))
    )
    (net (code "16") (name "Net-(D1-VOUT)") (class "Default")
      (node (ref "C23") (pin "1") (pinfunction "1_1") (pintype "power_in"))
      (node (ref "D1") (pin "3") (pinfunction "VOUT_3") (pintype "output"))
      (node (ref "R5") (pin "2") (pinfunction "2_2") (pintype "passive"))
    )
    (net (code "17") (name "Net-(D2-IN+)") (class "Default")
      (node (ref "D2") (pin "3") (pinfunction "IN+_3") (pintype "input"))
      (node (ref "R4") (pin "1") (pinfunction "1_1") (pintype "passive"))
    )
    (net (code "18") (name "Net-(D2-IN-)") (class "Default")
      (node (ref "D2") (pin "4") (pinfunction "IN-_4") (pintype "input"))
      (node (ref "R1") (pin "1") (pinfunction "1_1") (pintype "passive"))
    )
    (net (code "19") (name "Net-(D3-IN+)") (class "Default")
      (node (ref "D3") (pin "3") (pinfunction "IN+_3") (pintype "input"))
      (node (ref "R5") (pin "1") (pinfunction "1_1") (pintype "passive"))
    )
    (net (code "20") (name "Net-(D3-IN-)") (class "Default")
      (node (ref "D3") (pin "4") (pinfunction "IN-_4") (pintype "input"))
      (node (ref "R2") (pin "1") (pinfunction "1_1") (pintype "passive"))
    )
    (net (code "21") (name "Net-(D4-IN+)") (class "Default")
      (node (ref "D4") (pin "3") (pinfunction "IN+_3") (pintype "input"))
      (node (ref "R11") (pin "1") (pinfunction "1_1") (pintype "passive"))
      (node (ref "R7") (pin "1") (pinfunction "1_1") (pintype "passive"))
    )
    (net (code "22") (name "Net-(D4-IN-)") (class "Default")
      (node (ref "C28") (pin "1") (pinfunction "1_1") (pintype "power_in"))
      (node (ref "D4") (pin "4") (pinfunction "IN-_4") (pintype "input"))
      (node (ref "R8") (pin "2") (pinfunction "2_2") (pintype "passive"))
    )
    (net (code "23") (name "Net-(D4-OUT)") (class "Default")
      (node (ref "D4") (pin "1") (pinfunction "OUT_1") (pintype "output"))
      (node (ref "R13") (pin "1") (pinfunction "1_1") (pintype "passive"))
      (node (ref "R14") (pin "2") (pinfunction "2_2") (pintype "passive"))
    )
    (net (code "24") (name "Net-(D5-IN+)") (class "Default")
      (node (ref "C26") (pin "1") (pinfunction "1_1") (pintype "power_in"))
      (node (ref "D5") (pin "3") (pinfunction "IN+_3") (pintype "input"))
      (node (ref "R10") (pin "2") (pinfunction "2_2") (pintype "passive"))
    )
    (net (code "25") (name "Net-(D5-IN-)") (class "Default")
      (node (ref "D5") (pin "4") (pinfunction "IN-_4") (pintype "input"))
      (node (ref "R12") (pin "1") (pinfunction "1_1") (pintype "passive"))
      (node (ref "R9") (pin "1") (pinfunction "1_1") (pintype "passive"))
    )
    (net (code "26") (name "Net-(D5-OUT)") (class "Default")
      (node (ref "D5") (pin "1") (pinfunction "OUT_1") (pintype "output"))
      (node (ref "R8") (pin "1") (pinfunction "1_1") (pintype "passive"))
      (node (ref "R9") (pin "2") (pinfunction "2_2") (pintype "passive"))
    )
    (net (code "27") (name "Net-(D6-CS)") (class "Default")
      (node (ref "D6") (pin "1") (pinfunction "CS_1") (pintype "output"))
      (node (ref "R10") (pin "1") (pinfunction "1_1") (pintype "passive"))
    )
    (net (code "28") (name "Net-(D6-GATE)") (class "Default")
      (node (ref "D6") (pin "3") (pinfunction "GATE_3") (pintype "input"))
      (node (ref "R15") (pin "1") (pinfunction "1_1") (pintype "passive"))
      (node (ref "R25") (pin "2") (pinfunction "2_2") (pintype "passive"))
      (node (ref "VD11") (pin "1") (pinfunction "1_1") (pintype "passive"))
      (node (ref "VD19") (pin "2") (pinfunction "C_2") (pintype "passive"))
      (node (ref "VT1") (pin "1") (pinfunction "G_1") (pintype "passive"))
    )
    (net (code "29") (name "Net-(D6-VS)") (class "Default")
      (node (ref "D6") (pin "5") (pinfunction "VS_5") (pintype "power_in"))
      (node (ref "T1") (pin "1") (pinfunction "1_1") (pintype "power_in"))
      (node (ref "T4") (pin "1") (pinfunction "1_1") (pintype "power_in"))
      (node (ref "VD10") (pin "2") (pinfunction "C_2") (pintype "passive"))
      (node (ref "VD3") (pin "2") (pinfunction "C_2") (pintype "passive"))
      (node (ref "VD4") (pin "2") (pinfunction "C_2") (pintype "passive"))
      (node (ref "VD5") (pin "2") (pinfunction "C_2") (pintype "passive"))
      (node (ref "VD6") (pin "2") (pinfunction "C_2") (pintype "passive"))
      (node (ref "VD7") (pin "2") (pinfunction "C_2") (pintype "passive"))
      (node (ref "VD8") (pin "2") (pinfunction "C_2") (pintype "passive"))
      (node (ref "VD9") (pin "2") (pinfunction "C_2") (pintype "passive"))
      (node (ref "VT1") (pin "2") (pinfunction "D_2") (pintype "passive"))
      (node (ref "VT2") (pin "2") (pinfunction "D_2") (pintype "passive"))
      (node (ref "VT3") (pin "2") (pinfunction "D_2") (pintype "passive"))
      (node (ref "VT4") (pin "2") (pinfunction "D_2") (pintype "passive"))
      (node (ref "VT5") (pin "2") (pinfunction "D_2") (pintype "passive"))
      (node (ref "VT6") (pin "2") (pinfunction "D_2") (pintype "passive"))
      (node (ref "VT7") (pin "2") (pinfunction "D_2") (pintype "passive"))
      (node (ref "VT8") (pin "2") (pinfunction "D_2") (pintype "passive"))
    )
    (net (code "30") (name "Net-(D7-EN)") (class "Default")
      (node (ref "D7") (pin "3") (pinfunction "EN_3") (pintype "input"))
      (node (ref "R14") (pin "1") (pinfunction "1_1") (pintype "passive"))
    )
    (net (code "31") (name "Net-(D7-IN)") (class "Default")
      (node (ref "C30") (pin "1") (pinfunction "1_1") (pintype "power_in"))
      (node (ref "D7") (pin "2") (pinfunction "IN_2") (pintype "input"))
      (node (ref "R23") (pin "1") (pinfunction "1_1") (pintype "passive"))
      (node (ref "R24") (pin "2") (pinfunction "2_2") (pintype "passive"))
    )
    (net (code "32") (name "Net-(D7-OUT-Pad6)") (class "Default")
      (node (ref "D7") (pin "6") (pinfunction "OUT_6") (pintype "output"))
      (node (ref "D7") (pin "7") (pinfunction "OUT_7") (pintype "output"))
      (node (ref "R15") (pin "2") (pinfunction "2_2") (pintype "passive"))
      (node (ref "R16") (pin "2") (pinfunction "2_2") (pintype "passive"))
      (node (ref "R17") (pin "2") (pinfunction "2_2") (pintype "passive"))
      (node (ref "R18") (pin "2") (pinfunction "2_2") (pintype "passive"))
      (node (ref "R19") (pin "2") (pinfunction "2_2") (pintype "passive"))
      (node (ref "R20") (pin "2") (pinfunction "2_2") (pintype "passive"))
      (node (ref "R21") (pin "2") (pinfunction "2_2") (pintype "passive"))
      (node (ref "R22") (pin "2") (pinfunction "2_2") (pintype "passive"))
      (node (ref "VD11") (pin "2") (pinfunction "2_2") (pintype "passive"))
      (node (ref "VD12") (pin "2") (pinfunction "2_2") (pintype "passive"))
      (node (ref "VD13") (pin "2") (pinfunction "2_2") (pintype "passive"))
      (node (ref "VD14") (pin "2") (pinfunction "2_2") (pintype "passive"))
      (node (ref "VD15") (pin "2") (pinfunction "2_2") (pintype "passive"))
      (node (ref "VD16") (pin "2") (pinfunction "2_2") (pintype "passive"))
      (node (ref "VD17") (pin "2") (pinfunction "2_2") (pintype "passive"))
      (node (ref "VD18") (pin "2") (pinfunction "2_2") (pintype "passive"))
      (node (ref "VD2") (pin "1") (pinfunction "1_1") (pintype "passive"))
      (node (ref "VD20") (pin "2") (pinfunction "2_2") (pintype "passive"))
    )
    (net (code "33") (name "Net-(D8-IN+)") (class "Default")
      (node (ref "D8") (pin "3") (pinfunction "IN+_3") (pintype "input"))
      (node (ref "R33") (pin "1") (pinfunction "1_1") (pintype "passive"))
      (node (ref "R37") (pin "1") (pinfunction "1_1") (pintype "passive"))
    )
    (net (code "34") (name "Net-(D8-IN-)") (class "Default")
      (node (ref "C37") (pin "1") (pinfunction "1_1") (pintype "power_in"))
      (node (ref "D8") (pin "4") (pinfunction "IN-_4") (pintype "input"))
      (node (ref "R34") (pin "2") (pinfunction "2_2") (pintype "passive"))
    )
    (net (code "35") (name "Net-(D8-OUT)") (class "Default")
      (node (ref "D8") (pin "1") (pinfunction "OUT_1") (pintype "output"))
      (node (ref "R39") (pin "1") (pinfunction "1_1") (pintype "passive"))
      (node (ref "R40") (pin "2") (pinfunction "2_2") (pintype "passive"))
    )
    (net (code "36") (name "Net-(D9-IN+)") (class "Default")
      (node (ref "C35") (pin "1") (pinfunction "1_1") (pintype "power_in"))
      (node (ref "D9") (pin "3") (pinfunction "IN+_3") (pintype "input"))
      (node (ref "R36") (pin "2") (pinfunction "2_2") (pintype "passive"))
    )
    (net (code "37") (name "Net-(D9-IN-)") (class "Default")
      (node (ref "D9") (pin "4") (pinfunction "IN-_4") (pintype "input"))
      (node (ref "R35") (pin "1") (pinfunction "1_1") (pintype "passive"))
      (node (ref "R38") (pin "1") (pinfunction "1_1") (pintype "passive"))
    )
    (net (code "38") (name "Net-(D9-OUT)") (class "Default")
      (node (ref "D9") (pin "1") (pinfunction "OUT_1") (pintype "output"))
      (node (ref "R34") (pin "1") (pinfunction "1_1") (pintype "passive"))
      (node (ref "R35") (pin "2") (pinfunction "2_2") (pintype "passive"))
    )
    (net (code "39") (name "Net-(D10-CS)") (class "Default")
      (node (ref "D10") (pin "1") (pinfunction "CS_1") (pintype "output"))
      (node (ref "R36") (pin "1") (pinfunction "1_1") (pintype "passive"))
    )
    (net (code "40") (name "Net-(D10-GATE)") (class "Default")
      (node (ref "D10") (pin "3") (pinfunction "GATE_3") (pintype "input"))
      (node (ref "R41") (pin "1") (pinfunction "1_1") (pintype "passive"))
      (node (ref "R51") (pin "2") (pinfunction "2_2") (pintype "passive"))
      (node (ref "VD37") (pin "1") (pinfunction "1_1") (pintype "passive"))
      (node (ref "VD45") (pin "2") (pinfunction "C_2") (pintype "passive"))
      (node (ref "VT9") (pin "1") (pinfunction "G_1") (pintype "passive"))
    )
    (net (code "41") (name "Net-(D10-VS)") (class "Default")
      (node (ref "D10") (pin "5") (pinfunction "VS_5") (pintype "power_in"))
      (node (ref "T1") (pin "3") (pinfunction "3_3") (pintype "power_in"))
      (node (ref "T4") (pin "3") (pinfunction "3_3") (pintype "power_in"))
      (node (ref "VD29") (pin "2") (pinfunction "C_2") (pintype "passive"))
      (node (ref "VD30") (pin "2") (pinfunction "C_2") (pintype "passive"))
      (node (ref "VD31") (pin "2") (pinfunction "C_2") (pintype "passive"))
      (node (ref "VD32") (pin "2") (pinfunction "C_2") (pintype "passive"))
      (node (ref "VD33") (pin "2") (pinfunction "C_2") (pintype "passive"))
      (node (ref "VD34") (pin "2") (pinfunction "C_2") (pintype "passive"))
      (node (ref "VD35") (pin "2") (pinfunction "C_2") (pintype "passive"))
      (node (ref "VD36") (pin "2") (pinfunction "C_2") (pintype "passive"))
      (node (ref "VT10") (pin "2") (pinfunction "D_2") (pintype "passive"))
      (node (ref "VT11") (pin "2") (pinfunction "D_2") (pintype "passive"))
      (node (ref "VT12") (pin "2") (pinfunction "D_2") (pintype "passive"))
      (node (ref "VT13") (pin "2") (pinfunction "D_2") (pintype "passive"))
      (node (ref "VT14") (pin "2") (pinfunction "D_2") (pintype "passive"))
      (node (ref "VT15") (pin "2") (pinfunction "D_2") (pintype "passive"))
      (node (ref "VT16") (pin "2") (pinfunction "D_2") (pintype "passive"))
      (node (ref "VT9") (pin "2") (pinfunction "D_2") (pintype "passive"))
    )
    (net (code "42") (name "Net-(D11-EN)") (class "Default")
      (node (ref "D11") (pin "3") (pinfunction "EN_3") (pintype "input"))
      (node (ref "R40") (pin "1") (pinfunction "1_1") (pintype "passive"))
    )
    (net (code "43") (name "Net-(D11-IN)") (class "Default")
      (node (ref "C39") (pin "1") (pinfunction "1_1") (pintype "power_in"))
      (node (ref "D11") (pin "2") (pinfunction "IN_2") (pintype "input"))
      (node (ref "R49") (pin "1") (pinfunction "1_1") (pintype "passive"))
      (node (ref "R50") (pin "2") (pinfunction "2_2") (pintype "passive"))
    )
    (net (code "44") (name "Net-(D11-OUT-Pad6)") (class "Default")
      (node (ref "D11") (pin "6") (pinfunction "OUT_6") (pintype "output"))
      (node (ref "D11") (pin "7") (pinfunction "OUT_7") (pintype "output"))
      (node (ref "R41") (pin "2") (pinfunction "2_2") (pintype "passive"))
      (node (ref "R42") (pin "2") (pinfunction "2_2") (pintype "passive"))
      (node (ref "R43") (pin "2") (pinfunction "2_2") (pintype "passive"))
      (node (ref "R44") (pin "2") (pinfunction "2_2") (pintype "passive"))
      (node (ref "R45") (pin "2") (pinfunction "2_2") (pintype "passive"))
      (node (ref "R46") (pin "2") (pinfunction "2_2") (pintype "passive"))
      (node (ref "R47") (pin "2") (pinfunction "2_2") (pintype "passive"))
      (node (ref "R48") (pin "2") (pinfunction "2_2") (pintype "passive"))
      (node (ref "VD28") (pin "1") (pinfunction "1_1") (pintype "passive"))
      (node (ref "VD37") (pin "2") (pinfunction "2_2") (pintype "passive"))
      (node (ref "VD38") (pin "2") (pinfunction "2_2") (pintype "passive"))
      (node (ref "VD39") (pin "2") (pinfunction "2_2") (pintype "passive"))
      (node (ref "VD40") (pin "2") (pinfunction "2_2") (pintype "passive"))
      (node (ref "VD41") (pin "2") (pinfunction "2_2") (pintype "passive"))
      (node (ref "VD42") (pin "2") (pinfunction "2_2") (pintype "passive"))
      (node (ref "VD43") (pin "2") (pinfunction "2_2") (pintype "passive"))
      (node (ref "VD44") (pin "2") (pinfunction "2_2") (pintype "passive"))
      (node (ref "VD46") (pin "2") (pinfunction "2_2") (pintype "passive"))
    )
    (net (code "45") (name "Net-(D12-COMP)") (class "Default")
      (node (ref "C56") (pin "2") (pinfunction "2_2") (pintype "power_in"))
      (node (ref "D12") (pin "1") (pinfunction "COMP_1") (pintype "passive"))
      (node (ref "U1") (pin "4") (pinfunction "C_4") (pintype "passive"))
    )
    (net (code "46") (name "Net-(D12-ISENSE)") (class "Default")
      (node (ref "C59") (pin "1") (pinfunction "1_1") (pintype "power_in"))
      (node (ref "D12") (pin "3") (pinfunction "ISENSE_3") (pintype "passive"))
      (node (ref "R73") (pin "1") (pinfunction "1_1") (pintype "passive"))
    )
    (net (code "47") (name "Net-(D12-OUTPUT)") (class "Default")
      (node (ref "D12") (pin "6") (pinfunction "OUTPUT_6") (pintype "passive"))
      (node (ref "R72") (pin "2") (pinfunction "2_2") (pintype "passive"))
      (node (ref "VD62") (pin "2") (pinfunction "2_2") (pintype "passive"))
    )
    (net (code "48") (name "Net-(D12-RT{slash}CT)") (class "Default")
      (node (ref "C57") (pin "2") (pinfunction "2_2") (pintype "power_in"))
      (node (ref "D12") (pin "4") (pinfunction "RT/CT_4") (pintype "passive"))
      (node (ref "R68") (pin "2") (pinfunction "2_2") (pintype "passive"))
    )
    (net (code "49") (name "Net-(D12-VREF)") (class "Default")
      (node (ref "D12") (pin "8") (pinfunction "VREF_8") (pintype "passive"))
      (node (ref "R68") (pin "1") (pinfunction "1_1") (pintype "passive"))
    )
    (net (code "50") (name "Net-(D13-IN)") (class "Default")
      (node (ref "C60") (pin "2") (pinfunction "2_2") (pintype "power_in"))
      (node (ref "D13") (pin "3") (pinfunction "IN_3") (pintype "power_in"))
      (node (ref "FB1") (pin "1") (pinfunction "1_1") (pintype "passive"))
    )
    (net (code "51") (name "Net-(D14-DRIVER)") (class "Default")
      (node (ref "D14") (pin "1") (pinfunction "SW_1") (pintype "passive"))
      (node (ref "D14") (pin "7") (pinfunction "ISENSE_7") (pintype "input"))
      (node (ref "D14") (pin "8") (pinfunction "DRIVER_8") (pintype "passive"))
      (node (ref "R76") (pin "1") (pinfunction "1_1") (pintype "passive"))
    )
    (net (code "52") (name "Net-(D14-FB)") (class "Default")
      (node (ref "C66") (pin "2") (pinfunction "2_2") (pintype "power_in"))
      (node (ref "D14") (pin "5") (pinfunction "FB_5") (pintype "input"))
      (node (ref "R78") (pin "1") (pinfunction "1_1") (pintype "passive"))
      (node (ref "R80") (pin "1") (pinfunction "1_1") (pintype "passive"))
    )
    (net (code "53") (name "Net-(D14-SE)") (class "Default")
      (node (ref "D14") (pin "2") (pinfunction "SE_2") (pintype "passive"))
      (node (ref "L2") (pin "2") (pinfunction "2_2") (pintype "passive"))
      (node (ref "VD64") (pin "2") (pinfunction "2_2") (pintype "passive"))
    )
    (net (code "54") (name "Net-(D14-TC)") (class "Default")
      (node (ref "C67") (pin "1") (pinfunction "1_1") (pintype "power_in"))
      (node (ref "D14") (pin "3") (pinfunction "TC_3") (pintype "passive"))
    )
    (net (code "55") (name "Net-(D15-DRIVER)") (class "Default")
      (node (ref "D15") (pin "1") (pinfunction "SW_1") (pintype "passive"))
      (node (ref "D15") (pin "7") (pinfunction "ISENSE_7") (pintype "input"))
      (node (ref "D15") (pin "8") (pinfunction "DRIVER_8") (pintype "passive"))
      (node (ref "R77") (pin "1") (pinfunction "1_1") (pintype "passive"))
    )
    (net (code "56") (name "Net-(D15-FB)") (class "Default")
      (node (ref "C73") (pin "2") (pinfunction "2_2") (pintype "power_in"))
      (node (ref "D15") (pin "5") (pinfunction "FB_5") (pintype "input"))
      (node (ref "R79") (pin "1") (pinfunction "1_1") (pintype "passive"))
      (node (ref "R81") (pin "1") (pinfunction "1_1") (pintype "passive"))
    )
    (net (code "57") (name "Net-(D15-SE)") (class "Default")
      (node (ref "D15") (pin "2") (pinfunction "SE_2") (pintype "passive"))
      (node (ref "L3") (pin "2") (pinfunction "2_2") (pintype "passive"))
      (node (ref "VD65") (pin "2") (pinfunction "2_2") (pintype "passive"))
    )
    (net (code "58") (name "Net-(D15-TC)") (class "Default")
      (node (ref "C74") (pin "1") (pinfunction "1_1") (pintype "power_in"))
      (node (ref "D15") (pin "3") (pinfunction "TC_3") (pintype "passive"))
    )
    (net (code "59") (name "Net-(D16-IN)") (class "Default")
      (node (ref "C63") (pin "2") (pinfunction "2_2") (pintype "power_in"))
      (node (ref "D16") (pin "3") (pinfunction "IN_3") (pintype "power_in"))
      (node (ref "FB2") (pin "1") (pinfunction "1_1") (pintype "passive"))
    )
    (net (code "60") (name "Net-(D17-IN)") (class "Default")
      (node (ref "C78") (pin "2") (pinfunction "2_2") (pintype "power_in"))
      (node (ref "D17") (pin "3") (pinfunction "IN_3") (pintype "power_in"))
      (node (ref "FB3") (pin "1") (pinfunction "1_1") (pintype "passive"))
    )
    (net (code "61") (name "Net-(L1-Pad1)") (class "Default")
      (node (ref "L1") (pin "1") (pinfunction "1_1") (pintype "passive"))
      (node (ref "VD54") (pin "2") (pinfunction "2_2") (pintype "passive"))
      (node (ref "VD55") (pin "2") (pinfunction "2_2") (pintype "passive"))
    )
    (net (code "62") (name "Net-(R59-Pad2)") (class "Default")
      (node (ref "R59") (pin "2") (pinfunction "2_2") (pintype "passive"))
      (node (ref "R63") (pin "1") (pinfunction "1_1") (pintype "passive"))
    )
    (net (code "63") (name "Net-(T1-Pad4)") (class "Default")
      (node (ref "T1") (pin "4") (pinfunction "4_4") (pintype "power_in"))
      (node (ref "T4") (pin "4") (pinfunction "4_4") (pintype "power_in"))
      (node (ref "VD54") (pin "1") (pinfunction "1_1") (pintype "passive"))
      (node (ref "VD60") (pin "2") (pinfunction "2_2") (pintype "passive"))
    )
    (net (code "64") (name "Net-(T1-Pad6)") (class "Default")
      (node (ref "T1") (pin "6") (pinfunction "6_6") (pintype "power_in"))
      (node (ref "T4") (pin "6") (pinfunction "6_6") (pintype "power_in"))
    )
    (net (code "65") (name "Net-(T2-Pad4)") (class "Default")
      (node (ref "T2") (pin "4") (pinfunction "4_4") (pintype "power_in"))
      (node (ref "T2") (pin "5") (pinfunction "5_5") (pintype "power_in"))
      (node (ref "VD59") (pin "1") (pinfunction "1_1") (pintype "passive"))
    )
    (net (code "66") (name "Net-(T2-Pad6)") (class "Default")
      (node (ref "T2") (pin "6") (pinfunction "6_6") (pintype "power_in"))
      (node (ref "VD56") (pin "1") (pinfunction "1_1") (pintype "passive"))
    )
    (net (code "67") (name "Net-(U1A-A)") (class "Default")
      (node (ref "R61") (pin "1") (pinfunction "1_1") (pintype "passive"))
      (node (ref "R62") (pin "2") (pinfunction "2_2") (pintype "passive"))
      (node (ref "U1") (pin "1") (pinfunction "A_1") (pintype "passive"))
    )
    (net (code "68") (name "Net-(U1A-C)") (class "Default")
      (node (ref "C46") (pin "2") (pinfunction "2_2") (pintype "power_in"))
      (node (ref "R62") (pin "1") (pinfunction "1_1") (pintype "passive"))
      (node (ref "R66") (pin "1") (pinfunction "1_1") (pintype "passive"))
      (node (ref "U1") (pin "2") (pinfunction "C_2") (pintype "passive"))
      (node (ref "VD58") (pin "1") (pinfunction "1_1") (pintype "power_in"))
    )
    (net (code "69") (name "Net-(U2A-A)") (class "Default")
      (node (ref "R60") (pin "1") (pinfunction "1_1") (pintype "passive"))
      (node (ref "R64") (pin "2") (pinfunction "2_2") (pintype "passive"))
      (node (ref "U2") (pin "1") (pinfunction "A_1") (pintype "passive"))
    )
    (net (code "70") (name "Net-(U2A-C)") (class "Default")
      (node (ref "C47") (pin "2") (pinfunction "2_2") (pintype "power_in"))
      (node (ref "R64") (pin "1") (pinfunction "1_1") (pintype "passive"))
      (node (ref "R67") (pin "1") (pinfunction "1_1") (pintype "passive"))
      (node (ref "U2") (pin "2") (pinfunction "C_2") (pintype "passive"))
      (node (ref "VD57") (pin "1") (pinfunction "1_1") (pintype "power_in"))
    )
    (net (code "71") (name "Net-(VD1-C)") (class "Default")
      (node (ref "C1") (pin "2") (pinfunction "2_2") (pintype "power_in"))
      (node (ref "R3") (pin "2") (pinfunction "2_2") (pintype "passive"))
      (node (ref "R4") (pin "2") (pinfunction "2_2") (pintype "passive"))
      (node (ref "R6") (pin "1") (pinfunction "1_1") (pintype "passive"))
      (node (ref "VD1") (pin "2") (pinfunction "C_2") (pintype "passive"))
    )
    (net (code "72") (name "Net-(VD21-C)") (class "Default")
      (node (ref "R16") (pin "1") (pinfunction "1_1") (pintype "passive"))
      (node (ref "R26") (pin "2") (pinfunction "2_2") (pintype "passive"))
      (node (ref "VD12") (pin "1") (pinfunction "1_1") (pintype "passive"))
      (node (ref "VD21") (pin "2") (pinfunction "C_2") (pintype "passive"))
      (node (ref "VT2") (pin "1") (pinfunction "G_1") (pintype "passive"))
    )
    (net (code "73") (name "Net-(VD22-C)") (class "Default")
      (node (ref "R17") (pin "1") (pinfunction "1_1") (pintype "passive"))
      (node (ref "R27") (pin "2") (pinfunction "2_2") (pintype "passive"))
      (node (ref "VD13") (pin "1") (pinfunction "1_1") (pintype "passive"))
      (node (ref "VD22") (pin "2") (pinfunction "C_2") (pintype "passive"))
      (node (ref "VT3") (pin "1") (pinfunction "G_1") (pintype "passive"))
    )
    (net (code "74") (name "Net-(VD23-C)") (class "Default")
      (node (ref "R18") (pin "1") (pinfunction "1_1") (pintype "passive"))
      (node (ref "R28") (pin "2") (pinfunction "2_2") (pintype "passive"))
      (node (ref "VD14") (pin "1") (pinfunction "1_1") (pintype "passive"))
      (node (ref "VD23") (pin "2") (pinfunction "C_2") (pintype "passive"))
      (node (ref "VT4") (pin "1") (pinfunction "G_1") (pintype "passive"))
    )
    (net (code "75") (name "Net-(VD24-C)") (class "Default")
      (node (ref "R19") (pin "1") (pinfunction "1_1") (pintype "passive"))
      (node (ref "R29") (pin "2") (pinfunction "2_2") (pintype "passive"))
      (node (ref "VD15") (pin "1") (pinfunction "1_1") (pintype "passive"))
      (node (ref "VD24") (pin "2") (pinfunction "C_2") (pintype "passive"))
      (node (ref "VT5") (pin "1") (pinfunction "G_1") (pintype "passive"))
    )
    (net (code "76") (name "Net-(VD25-C)") (class "Default")
      (node (ref "R20") (pin "1") (pinfunction "1_1") (pintype "passive"))
      (node (ref "R30") (pin "2") (pinfunction "2_2") (pintype "passive"))
      (node (ref "VD16") (pin "1") (pinfunction "1_1") (pintype "passive"))
      (node (ref "VD25") (pin "2") (pinfunction "C_2") (pintype "passive"))
      (node (ref "VT6") (pin "1") (pinfunction "G_1") (pintype "passive"))
    )
    (net (code "77") (name "Net-(VD26-C)") (class "Default")
      (node (ref "R21") (pin "1") (pinfunction "1_1") (pintype "passive"))
      (node (ref "R31") (pin "2") (pinfunction "2_2") (pintype "passive"))
      (node (ref "VD17") (pin "1") (pinfunction "1_1") (pintype "passive"))
      (node (ref "VD26") (pin "2") (pinfunction "C_2") (pintype "passive"))
      (node (ref "VT7") (pin "1") (pinfunction "G_1") (pintype "passive"))
    )
    (net (code "78") (name "Net-(VD27-C)") (class "Default")
      (node (ref "R22") (pin "1") (pinfunction "1_1") (pintype "passive"))
      (node (ref "R32") (pin "2") (pinfunction "2_2") (pintype "passive"))
      (node (ref "VD18") (pin "1") (pinfunction "1_1") (pintype "passive"))
      (node (ref "VD27") (pin "2") (pinfunction "C_2") (pintype "passive"))
      (node (ref "VT8") (pin "1") (pinfunction "G_1") (pintype "passive"))
    )
    (net (code "79") (name "Net-(VD47-C)") (class "Default")
      (node (ref "R42") (pin "1") (pinfunction "1_1") (pintype "passive"))
      (node (ref "R52") (pin "2") (pinfunction "2_2") (pintype "passive"))
      (node (ref "VD38") (pin "1") (pinfunction "1_1") (pintype "passive"))
      (node (ref "VD47") (pin "2") (pinfunction "C_2") (pintype "passive"))
      (node (ref "VT10") (pin "1") (pinfunction "G_1") (pintype "passive"))
    )
    (net (code "80") (name "Net-(VD48-C)") (class "Default")
      (node (ref "R43") (pin "1") (pinfunction "1_1") (pintype "passive"))
      (node (ref "R53") (pin "2") (pinfunction "2_2") (pintype "passive"))
      (node (ref "VD39") (pin "1") (pinfunction "1_1") (pintype "passive"))
      (node (ref "VD48") (pin "2") (pinfunction "C_2") (pintype "passive"))
      (node (ref "VT11") (pin "1") (pinfunction "G_1") (pintype "passive"))
    )
    (net (code "81") (name "Net-(VD49-C)") (class "Default")
      (node (ref "R44") (pin "1") (pinfunction "1_1") (pintype "passive"))
      (node (ref "R54") (pin "2") (pinfunction "2_2") (pintype "passive"))
      (node (ref "VD40") (pin "1") (pinfunction "1_1") (pintype "passive"))
      (node (ref "VD49") (pin "2") (pinfunction "C_2") (pintype "passive"))
      (node (ref "VT12") (pin "1") (pinfunction "G_1") (pintype "passive"))
    )
    (net (code "82") (name "Net-(VD50-C)") (class "Default")
      (node (ref "R45") (pin "1") (pinfunction "1_1") (pintype "passive"))
      (node (ref "R55") (pin "2") (pinfunction "2_2") (pintype "passive"))
      (node (ref "VD41") (pin "1") (pinfunction "1_1") (pintype "passive"))
      (node (ref "VD50") (pin "2") (pinfunction "C_2") (pintype "passive"))
      (node (ref "VT13") (pin "1") (pinfunction "G_1") (pintype "passive"))
    )
    (net (code "83") (name "Net-(VD51-C)") (class "Default")
      (node (ref "R46") (pin "1") (pinfunction "1_1") (pintype "passive"))
      (node (ref "R56") (pin "2") (pinfunction "2_2") (pintype "passive"))
      (node (ref "VD42") (pin "1") (pinfunction "1_1") (pintype "passive"))
      (node (ref "VD51") (pin "2") (pinfunction "C_2") (pintype "passive"))
      (node (ref "VT14") (pin "1") (pinfunction "G_1") (pintype "passive"))
    )
    (net (code "84") (name "Net-(VD52-C)") (class "Default")
      (node (ref "R47") (pin "1") (pinfunction "1_1") (pintype "passive"))
      (node (ref "R57") (pin "2") (pinfunction "2_2") (pintype "passive"))
      (node (ref "VD43") (pin "1") (pinfunction "1_1") (pintype "passive"))
      (node (ref "VD52") (pin "2") (pinfunction "C_2") (pintype "passive"))
      (node (ref "VT15") (pin "1") (pinfunction "G_1") (pintype "passive"))
    )
    (net (code "85") (name "Net-(VD53-C)") (class "Default")
      (node (ref "R48") (pin "1") (pinfunction "1_1") (pintype "passive"))
      (node (ref "R58") (pin "2") (pinfunction "2_2") (pintype "passive"))
      (node (ref "VD44") (pin "1") (pinfunction "1_1") (pintype "passive"))
      (node (ref "VD53") (pin "2") (pinfunction "C_2") (pintype "passive"))
      (node (ref "VT16") (pin "1") (pinfunction "G_1") (pintype "passive"))
    )
    (net (code "86") (name "Net-(VD55-Pad1)") (class "Default")
      (node (ref "VD55") (pin "1") (pinfunction "1_1") (pintype "passive"))
      (node (ref "VD61") (pin "2") (pinfunction "2_2") (pintype "passive"))
    )
    (net (code "87") (name "Net-(VD63-C)") (class "Default")
      (node (ref "R72") (pin "1") (pinfunction "1_1") (pintype "passive"))
      (node (ref "R74") (pin "2") (pinfunction "2_2") (pintype "passive"))
      (node (ref "VD62") (pin "1") (pinfunction "1_1") (pintype "passive"))
      (node (ref "VD63") (pin "2") (pinfunction "C_2") (pintype "passive"))
      (node (ref "VT17") (pin "1") (pinfunction "G_1") (pintype "passive"))
    )
    (net (code "88") (name "Net-(VT17-D)") (class "Default")
      (node (ref "T2") (pin "2") (pinfunction "2_2") (pintype "power_in"))
      (node (ref "VT17") (pin "2") (pinfunction "D_2") (pintype "passive"))
    )
    (net (code "89") (name "Net-(VT17-S)") (class "Default")
      (node (ref "R73") (pin "2") (pinfunction "2_2") (pintype "passive"))
      (node (ref "R75") (pin "1") (pinfunction "1_1") (pintype "passive"))
      (node (ref "VT17") (pin "3") (pinfunction "S_3") (pintype "passive"))
    )
    (net (code "90") (name "VCCH_5V") (class "Default")
      (node (ref "C61") (pin "2") (pinfunction "2_2") (pintype "power_in"))
      (node (ref "D13") (pin "2") (pinfunction "OUT_2") (pintype "passive"))
      (node (ref "D13") (pin "4") (pinfunction "OUT_4") (pintype "passive"))
      (node (ref "R60") (pin "2") (pinfunction "2_2") (pintype "passive"))
    )
    (net (code "91") (name "VCCH_12V") (class "Default")
      (node (ref "C54") (pin "1") (pinfunction "1_1") (pintype "power_in"))
      (node (ref "C55") (pin "2") (pinfunction "2_2") (pintype "power_in"))
      (node (ref "R61") (pin "2") (pinfunction "2_2") (pintype "passive"))
      (node (ref "R65") (pin "1") (pinfunction "1_1") (pintype "passive"))
      (node (ref "VD56") (pin "2") (pinfunction "2_2") (pintype "passive"))
    )
    (net (code "92") (name "VCCH_380V") (class "Default")
      (node (ref "C48") (pin "1") (pinfunction "1_1") (pintype "power_in"))
      (node (ref "C49") (pin "1") (pinfunction "1_1") (pintype "power_in"))
      (node (ref "C50") (pin "1") (pinfunction "1_1") (pintype "power_in"))
      (node (ref "C51") (pin "1") (pinfunction "1_1") (pintype "power_in"))
      (node (ref "L1") (pin "2") (pinfunction "2_2") (pintype "passive"))
      (node (ref "R59") (pin "1") (pinfunction "1_1") (pintype "passive"))
    )
    (net (code "93") (name "VCC_3V3") (class "Default")
      (node (ref "C24") (pin "2") (pinfunction "2_2") (pintype "power_in"))
      (node (ref "C25") (pin "2") (pinfunction "2_2") (pintype "power_in"))
      (node (ref "C27") (pin "2") (pinfunction "2_2") (pintype "power_in"))
      (node (ref "C29") (pin "2") (pinfunction "2_2") (pintype "power_in"))
      (node (ref "C36") (pin "2") (pinfunction "2_2") (pintype "power_in"))
      (node (ref "C38") (pin "2") (pinfunction "2_2") (pintype "power_in"))
      (node (ref "C79") (pin "2") (pinfunction "2_2") (pintype "power_in"))
      (node (ref "D17") (pin "2") (pinfunction "OUT_2") (pintype "passive"))
      (node (ref "D17") (pin "4") (pinfunction "OUT_4") (pintype "passive"))
      (node (ref "D2") (pin "5") (pinfunction "VCC_5") (pintype "power_in"))
      (node (ref "D3") (pin "5") (pinfunction "VCC_5") (pintype "power_in"))
      (node (ref "D4") (pin "5") (pinfunction "VCC_5") (pintype "power_in"))
      (node (ref "D5") (pin "5") (pinfunction "VCC_5") (pintype "power_in"))
      (node (ref "D8") (pin "5") (pinfunction "VCC_5") (pintype "power_in"))
      (node (ref "D9") (pin "5") (pinfunction "VCC_5") (pintype "power_in"))
      (node (ref "R33") (pin "2") (pinfunction "2_2") (pintype "passive"))
      (node (ref "R7") (pin "2") (pinfunction "2_2") (pintype "passive"))
    )
    (net (code "94") (name "VCC_5V") (class "Default")
      (node (ref "C22") (pin "2") (pinfunction "2_2") (pintype "power_in"))
      (node (ref "C80") (pin "2") (pinfunction "2_2") (pintype "power_in"))
      (node (ref "D1") (pin "1") (pinfunction "VCC_1") (pintype "passive"))
      (node (ref "D16") (pin "2") (pinfunction "OUT_2") (pintype "passive"))
      (node (ref "D16") (pin "4") (pinfunction "OUT_4") (pintype "passive"))
    )
    (net (code "95") (name "VCC_12V") (class "Default")
      (node (ref "C31") (pin "2") (pinfunction "2_2") (pintype "power_in"))
      (node (ref "C32") (pin "2") (pinfunction "2_2") (pintype "power_in"))
      (node (ref "C33") (pin "1") (pinfunction "1_1") (pintype "power_in"))
      (node (ref "C34") (pin "1") (pinfunction "1_1") (pintype "power_in"))
      (node (ref "C40") (pin "2") (pinfunction "2_2") (pintype "power_in"))
      (node (ref "C41") (pin "2") (pinfunction "2_2") (pintype "power_in"))
      (node (ref "C42") (pin "1") (pinfunction "1_1") (pintype "power_in"))
      (node (ref "C43") (pin "1") (pinfunction "1_1") (pintype "power_in"))
      (node (ref "C68") (pin "1") (pinfunction "1_1") (pintype "power_in"))
      (node (ref "C69") (pin "2") (pinfunction "2_2") (pintype "power_in"))
      (node (ref "C70") (pin "2") (pinfunction "2_2") (pintype "power_in"))
      (node (ref "D11") (pin "1") (pinfunction "VDD_1") (pintype "passive"))
      (node (ref "D11") (pin "8") (pinfunction "VDD_8") (pintype "passive"))
      (node (ref "D7") (pin "1") (pinfunction "VDD_1") (pintype "passive"))
      (node (ref "D7") (pin "8") (pinfunction "VDD_8") (pintype "passive"))
      (node (ref "L2") (pin "1") (pinfunction "1_1") (pintype "passive"))
      (node (ref "R78") (pin "2") (pinfunction "2_2") (pintype "passive"))
      (node (ref "VD2") (pin "2") (pinfunction "2_2") (pintype "passive"))
      (node (ref "VD28") (pin "2") (pinfunction "2_2") (pintype "passive"))
    )
    (net (code "96") (name "VCC_IN") (class "Default")
      (node (ref "C58") (pin "1") (pinfunction "1_1") (pintype "power_in"))
      (node (ref "C64") (pin "2") (pinfunction "2_2") (pintype "power_in"))
      (node (ref "C65") (pin "2") (pinfunction "2_2") (pintype "power_in"))
      (node (ref "C71") (pin "2") (pinfunction "2_2") (pintype "power_in"))
      (node (ref "C72") (pin "2") (pinfunction "2_2") (pintype "power_in"))
      (node (ref "D1") (pin "5") (pinfunction "IP-_5") (pintype "passive"))
      (node (ref "D12") (pin "7") (pinfunction "VCC_7") (pintype "passive"))
      (node (ref "D14") (pin "6") (pinfunction "VCC_6") (pintype "power_in"))
      (node (ref "D15") (pin "6") (pinfunction "VCC_6") (pintype "power_in"))
      (node (ref "R76") (pin "2") (pinfunction "2_2") (pintype "passive"))
      (node (ref "R77") (pin "2") (pinfunction "2_2") (pintype "passive"))
      (node (ref "T1") (pin "2") (pinfunction "2_2") (pintype "power_in"))
      (node (ref "T2") (pin "1") (pinfunction "1_1") (pintype "power_in"))
      (node (ref "T4") (pin "2") (pinfunction "2_2") (pintype "power_in"))
    )
    (net (code "97") (name "unconnected-(T1-Pad5)") (class "Default")
      (node (ref "T1") (pin "5") (pinfunction "5_5") (pintype "power_in"))
    )
    (net (code "98") (name "unconnected-(T4-Pad5)") (class "Default")
      (node (ref "T4") (pin "5") (pinfunction "5_5") (pintype "power_in"))
    )
  )
)
